# main.net
KiCad netlist of a schematic drawn in Altium Designer
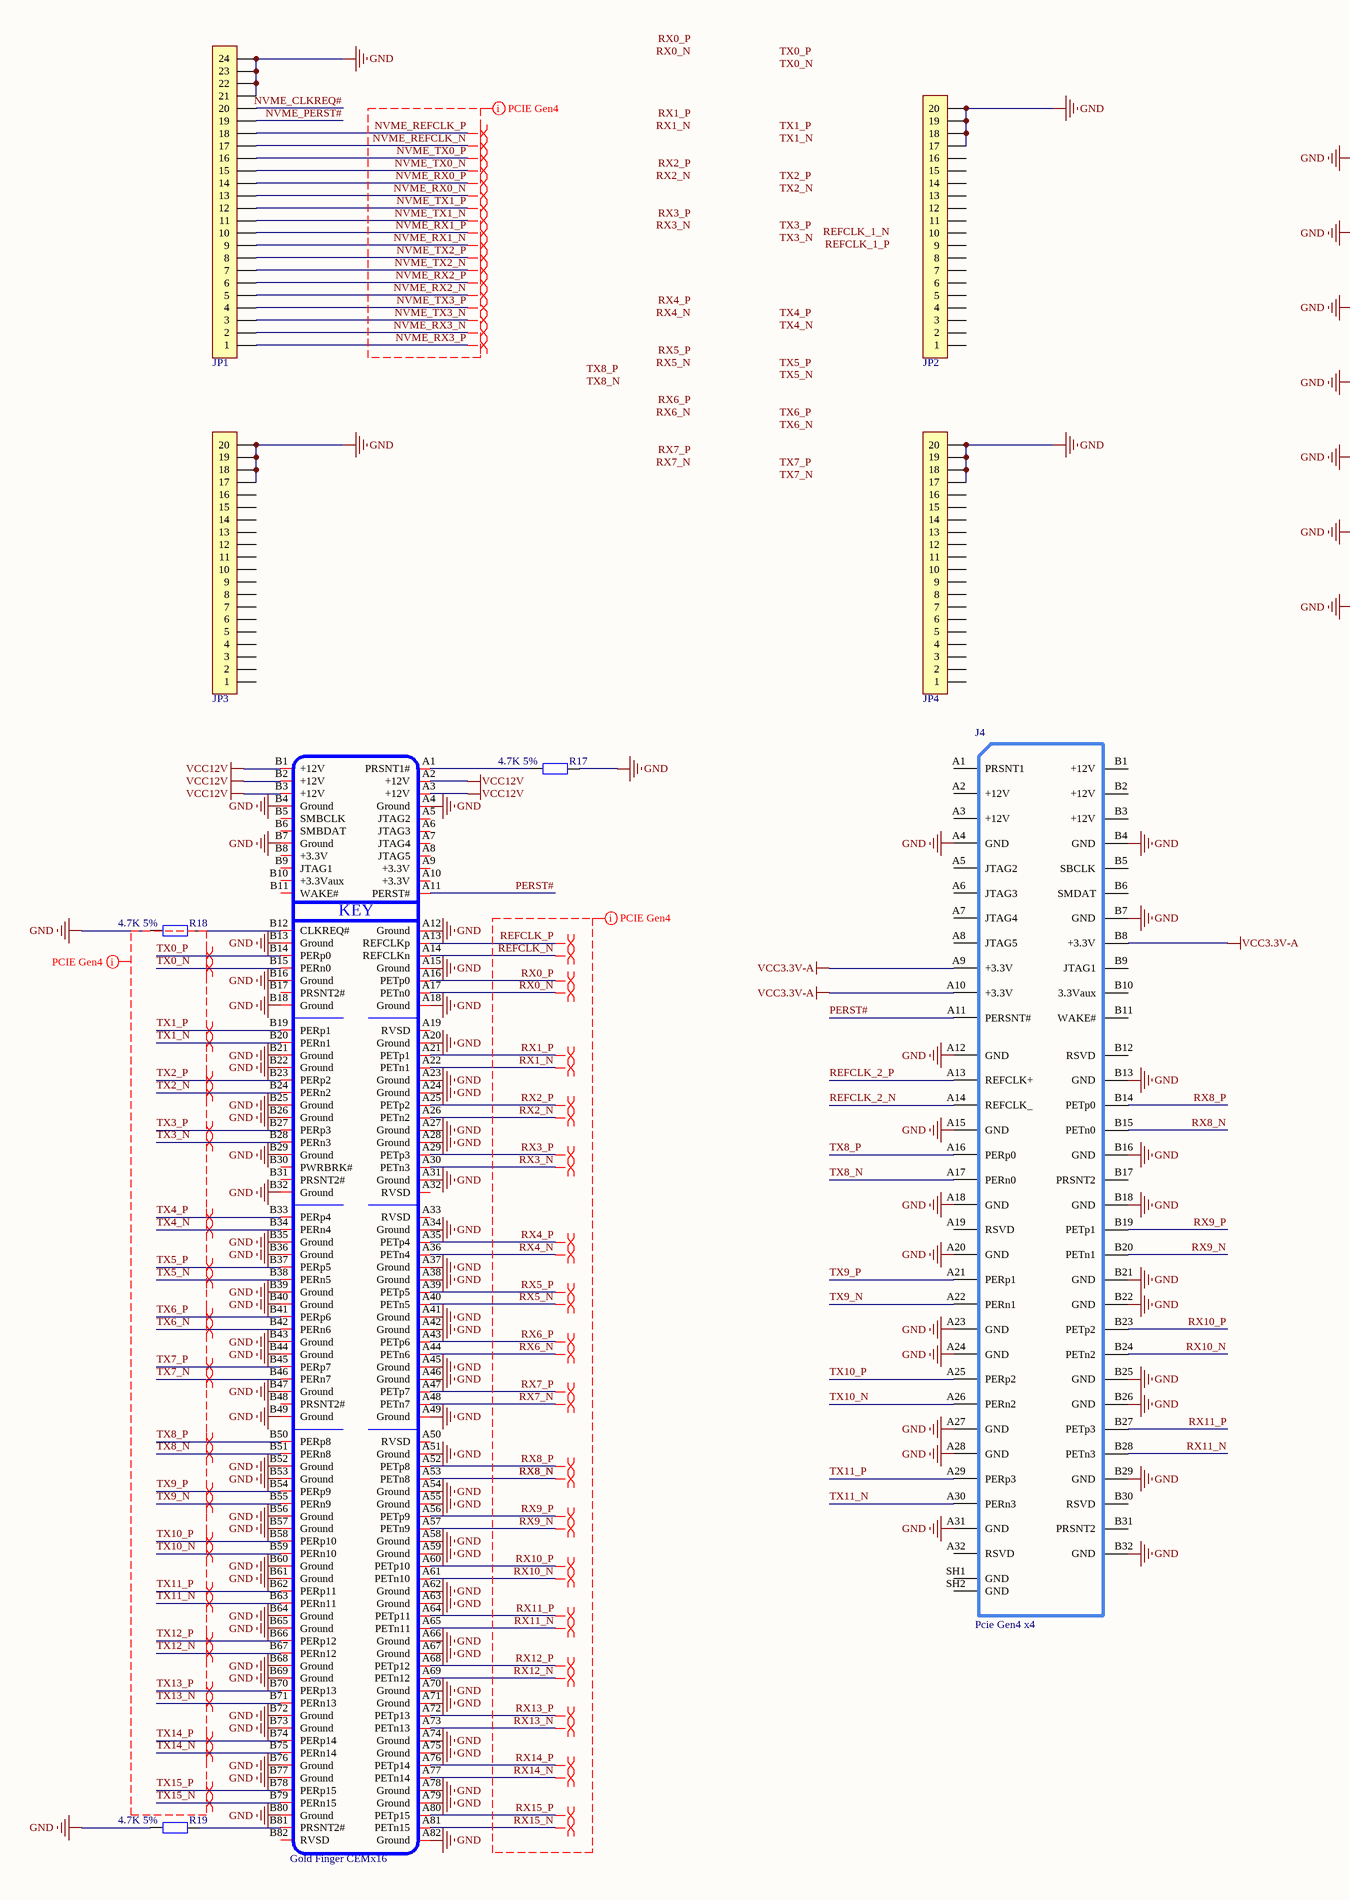
[diagram p0: main.SchDoc, left]
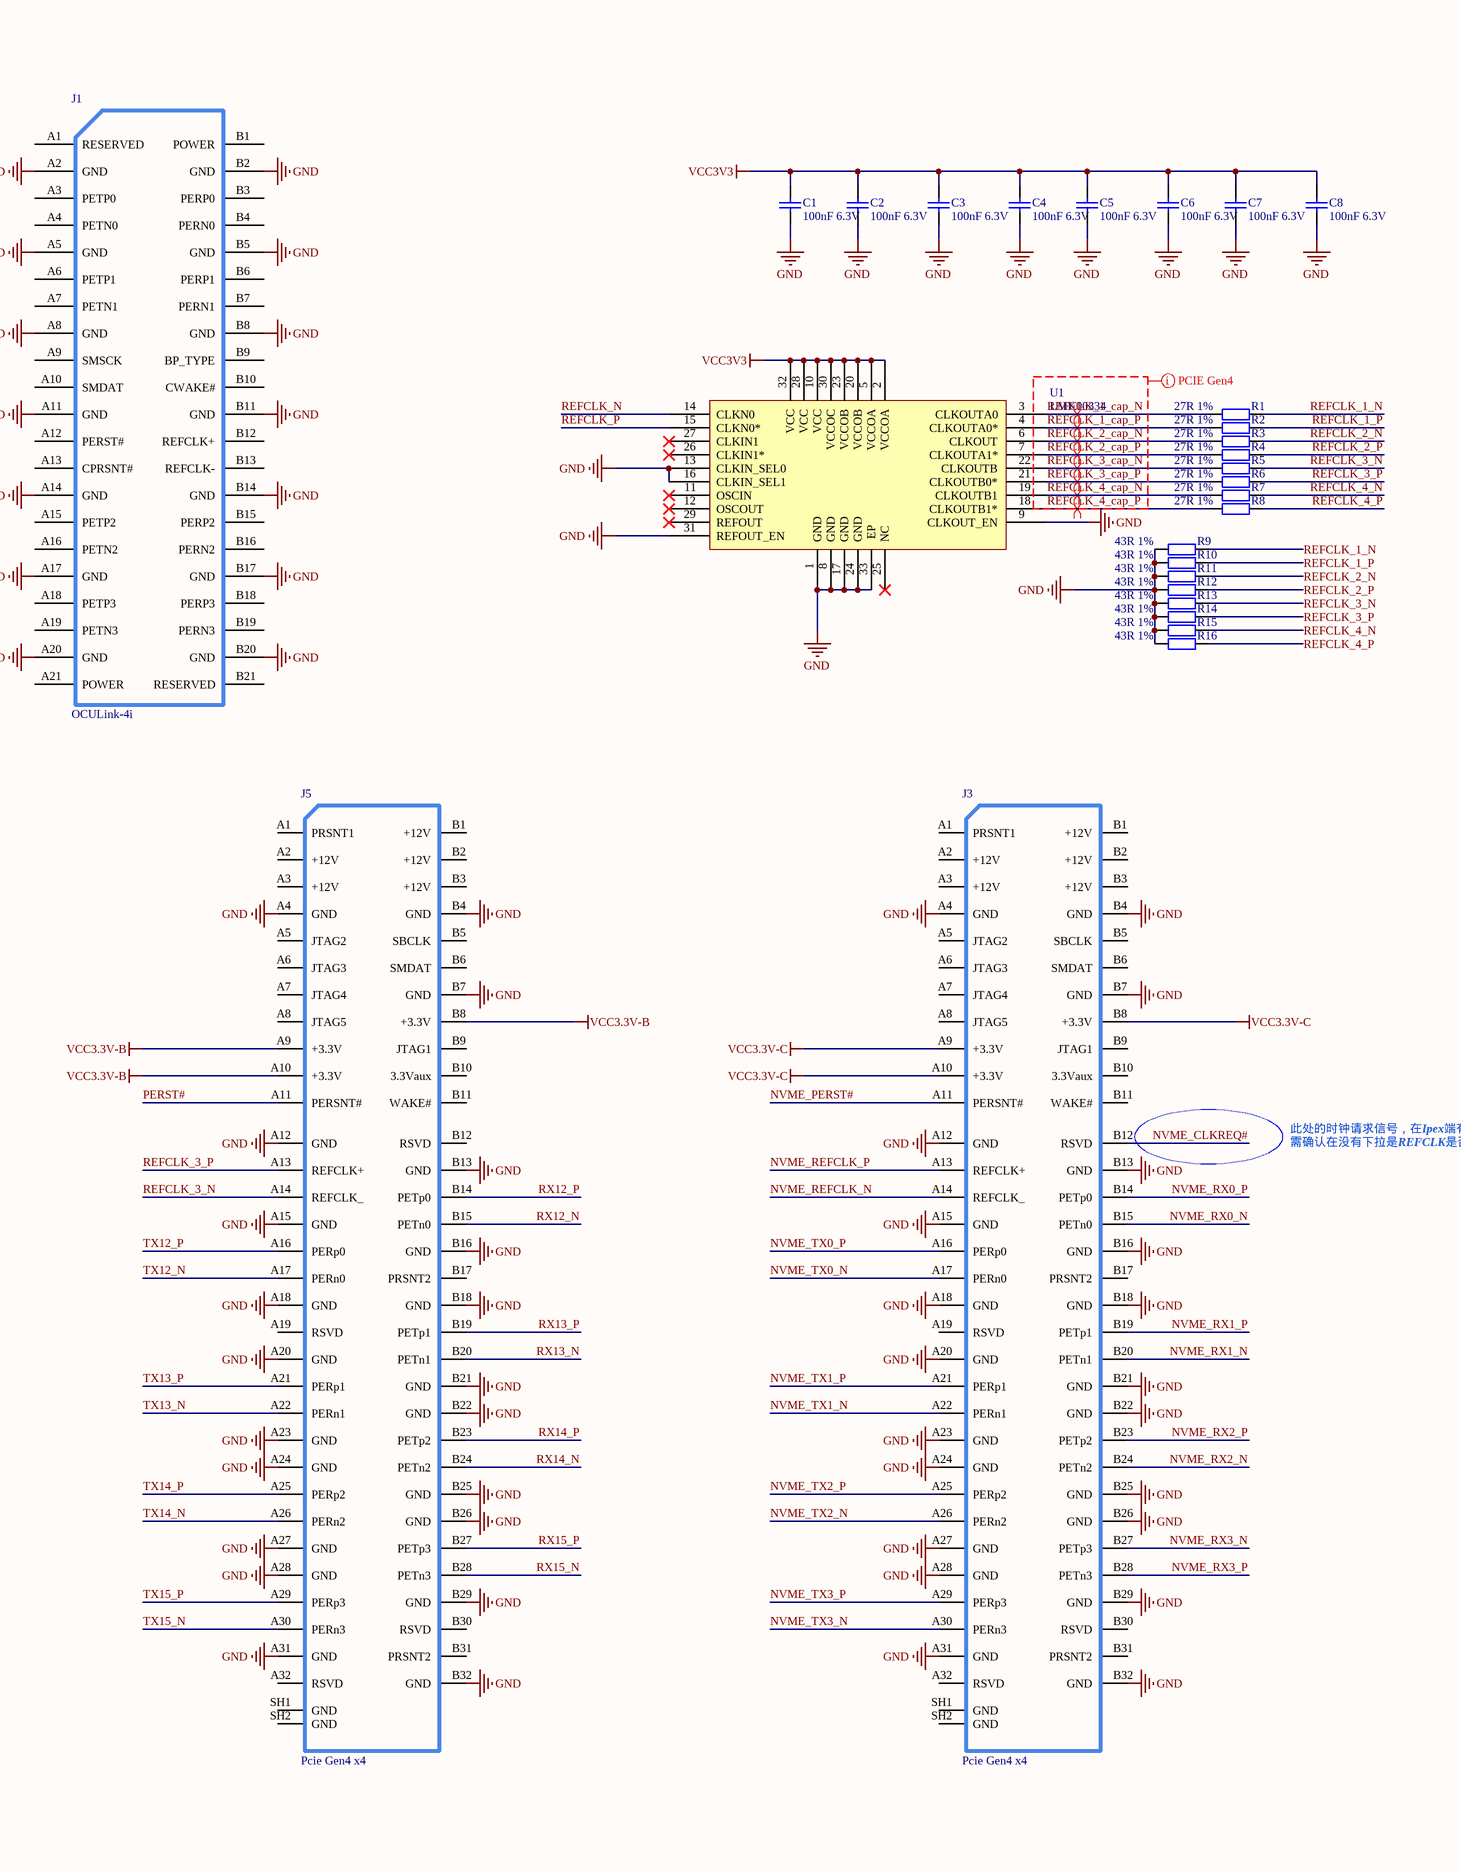
[diagram p1: main.SchDoc, right]

(export (version "E")
  (design (tool "Eeschema 10.0.6"))
  (components
    (comp (ref "C1")
      (value "100nF 6.3V")
      (footprint "c0603_l")
      (description "贴片电容/MLCC电容")
      (libsource (lib "Capacitors") (part "C"))
    )
    (comp (ref "C2")
      (value "100nF 6.3V")
      (footprint "c0603_l")
      (description "贴片电容/MLCC电容")
      (libsource (lib "Capacitors") (part "C"))
    )
    (comp (ref "C3")
      (value "100nF 6.3V")
      (footprint "c0603_l")
      (description "贴片电容/MLCC电容")
      (libsource (lib "Capacitors") (part "C"))
    )
    (comp (ref "C4")
      (value "100nF 6.3V")
      (footprint "c0603_l")
      (description "贴片电容/MLCC电容")
      (libsource (lib "Capacitors") (part "C"))
    )
    (comp (ref "C5")
      (value "100nF 6.3V")
      (footprint "c0603_l")
      (description "贴片电容/MLCC电容")
      (libsource (lib "Capacitors") (part "C"))
    )
    (comp (ref "C6")
      (value "100nF 6.3V")
      (footprint "c0603_l")
      (description "贴片电容/MLCC电容")
      (libsource (lib "Capacitors") (part "C"))
    )
    (comp (ref "C7")
      (value "100nF 6.3V")
      (footprint "c0603_l")
      (description "贴片电容/MLCC电容")
      (libsource (lib "Capacitors") (part "C"))
    )
    (comp (ref "C8")
      (value "100nF 6.3V")
      (footprint "c0603_l")
      (description "贴片电容/MLCC电容")
      (libsource (lib "Capacitors") (part "C"))
    )
    (comp (ref "J1")
      (value "OCULink-4i")
      (footprint "SFF8611_卧式")
      (libsource (lib "Connector-PCIE") (part "OCULink-4i"))
    )
    (comp (ref "J2")
      (value "Pcie Gen4 x16")
      (footprint "CON_PCI-E_164_M")
      (fields (field (name "DEVICE") "Gold Finger CEMx16"))
      (libsource (lib "Connector-PCIE") (part "Pcie Gen4 x16"))
    )
    (comp (ref "J3")
      (value "Pcie Gen4 x4")
      (footprint "PCIe Gen4 X4 贴片")
      (libsource (lib "Connector-PCIE") (part "Pcie Gen4 x4"))
    )
    (comp (ref "J4")
      (value "Pcie Gen4 x4")
      (footprint "PCIe Gen4 X4 贴片")
      (libsource (lib "Connector-PCIE") (part "Pcie Gen4 x4"))
    )
    (comp (ref "J5")
      (value "Pcie Gen4 x4")
      (footprint "PCIe Gen4 X4 贴片")
      (libsource (lib "Connector-PCIE") (part "Pcie Gen4 x4"))
    )
    (comp (ref "JP1")
      (value "FPC1.0-24P")
      (footprint "CONN-SMD_20P-P0.50_I-PEX_20455-020E-02")
      (description "FPC连接器")
      (fields (field (name "版权归属") "源创客"))
      (libsource (lib "Connector-FPC") (part "FPC-24P"))
    )
    (comp (ref "JP2")
      (value "FPC1.0-20P")
      (footprint "CONN-SMD_20P-P0.50_I-PEX_20455-020E-02")
      (description "FPC连接器")
      (fields (field (name "版权归属") "源创客"))
      (libsource (lib "Connector-FPC") (part "FPC-20P"))
    )
    (comp (ref "JP3")
      (value "FPC1.0-20P")
      (footprint "CONN-SMD_20P-P0.50_I-PEX_20455-020E-02")
      (description "FPC连接器")
      (fields (field (name "版权归属") "源创客"))
      (libsource (lib "Connector-FPC") (part "FPC-20P"))
    )
    (comp (ref "JP4")
      (value "FPC1.0-20P")
      (footprint "CONN-SMD_20P-P0.50_I-PEX_20455-020E-02")
      (description "FPC连接器")
      (fields (field (name "版权归属") "源创客"))
      (libsource (lib "Connector-FPC") (part "FPC-20P"))
    )
    (comp (ref "R1") (value "27R 1%") (footprint "r0402_l") (libsource (lib "Resistors") (part "R")))
    (comp (ref "R2") (value "27R 1%") (footprint "r0402_l") (libsource (lib "Resistors") (part "R")))
    (comp (ref "R3") (value "27R 1%") (footprint "r0402_l") (libsource (lib "Resistors") (part "R")))
    (comp (ref "R4") (value "27R 1%") (footprint "r0402_l") (libsource (lib "Resistors") (part "R")))
    (comp (ref "R5") (value "27R 1%") (footprint "r0402_l") (libsource (lib "Resistors") (part "R")))
    (comp (ref "R6") (value "27R 1%") (footprint "r0402_l") (libsource (lib "Resistors") (part "R")))
    (comp (ref "R7") (value "27R 1%") (footprint "r0402_l") (libsource (lib "Resistors") (part "R")))
    (comp (ref "R8") (value "27R 1%") (footprint "r0402_l") (libsource (lib "Resistors") (part "R")))
    (comp (ref "R9") (value "43R 1%") (footprint "r0402_l") (libsource (lib "Resistors") (part "R")))
    (comp (ref "R10") (value "43R 1%") (footprint "r0402_l") (libsource (lib "Resistors") (part "R")))
    (comp (ref "R11") (value "43R 1%") (footprint "r0402_l") (libsource (lib "Resistors") (part "R")))
    (comp (ref "R12") (value "43R 1%") (footprint "r0402_l") (libsource (lib "Resistors") (part "R")))
    (comp (ref "R13") (value "43R 1%") (footprint "r0402_l") (libsource (lib "Resistors") (part "R")))
    (comp (ref "R14") (value "43R 1%") (footprint "r0402_l") (libsource (lib "Resistors") (part "R")))
    (comp (ref "R15") (value "43R 1%") (footprint "r0402_l") (libsource (lib "Resistors") (part "R")))
    (comp (ref "R16") (value "43R 1%") (footprint "r0402_l") (libsource (lib "Resistors") (part "R")))
    (comp (ref "R17") (value "4.7K 5%") (footprint "r0402_l") (libsource (lib "Resistors") (part "R")))
    (comp (ref "R18") (value "4.7K 5%") (footprint "r0402_l") (libsource (lib "Resistors") (part "R")))
    (comp (ref "R19") (value "4.7K 5%") (footprint "r0402_l") (libsource (lib "Resistors") (part "R")))
    (comp (ref "U1") (value "LMK00334") (footprint "QFN32 5x5_N") (libsource (lib "时钟缓冲器") (part "LMK00334")))
  )
  (nets
    (net (code "1") (name "/NVME_CLKREQ#") (class "Default")
      (node (ref "J3") (pin "B12") (pinfunction "RSVD_B12") (pintype "passive"))
      (node (ref "JP1") (pin "20") (pinfunction "20_20") (pintype "passive"))
    )
    (net (code "2") (name "/NVME_PERST#") (class "Default")
      (node (ref "J3") (pin "A11") (pinfunction "PERSNT#_A11") (pintype "passive"))
      (node (ref "JP1") (pin "19") (pinfunction "19_19") (pintype "passive"))
    )
    (net (code "3") (name "/NVME_REFCLK_N") (class "Default")
      (node (ref "J3") (pin "A14") (pinfunction "REFCLK__A14") (pintype "passive"))
      (node (ref "JP1") (pin "17") (pinfunction "17_17") (pintype "passive"))
    )
    (net (code "4") (name "/NVME_REFCLK_P") (class "Default")
      (node (ref "J3") (pin "A13") (pinfunction "REFCLK+_A13") (pintype "passive"))
      (node (ref "JP1") (pin "18") (pinfunction "18_18") (pintype "passive"))
    )
    (net (code "5") (name "/NVME_RX0_N") (class "Default")
      (node (ref "J3") (pin "B15") (pinfunction "PETn0_B15") (pintype "passive"))
      (node (ref "JP1") (pin "13") (pinfunction "13_13") (pintype "passive"))
    )
    (net (code "6") (name "/NVME_RX0_P") (class "Default")
      (node (ref "J3") (pin "B14") (pinfunction "PETp0_B14") (pintype "passive"))
      (node (ref "JP1") (pin "14") (pinfunction "14_14") (pintype "passive"))
    )
    (net (code "7") (name "/NVME_RX1_N") (class "Default")
      (node (ref "J3") (pin "B20") (pinfunction "PETn1_B20") (pintype "passive"))
      (node (ref "JP1") (pin "9") (pinfunction "9_9") (pintype "passive"))
    )
    (net (code "8") (name "/NVME_RX1_P") (class "Default")
      (node (ref "J3") (pin "B19") (pinfunction "PETp1_B19") (pintype "passive"))
      (node (ref "JP1") (pin "10") (pinfunction "10_10") (pintype "passive"))
    )
    (net (code "9") (name "/NVME_RX2_N") (class "Default")
      (node (ref "J3") (pin "B24") (pinfunction "PETn2_B24") (pintype "passive"))
      (node (ref "JP1") (pin "5") (pinfunction "5_5") (pintype "passive"))
    )
    (net (code "10") (name "/NVME_RX2_P") (class "Default")
      (node (ref "J3") (pin "B23") (pinfunction "PETp2_B23") (pintype "passive"))
      (node (ref "JP1") (pin "6") (pinfunction "6_6") (pintype "passive"))
    )
    (net (code "11") (name "/NVME_RX3_N") (class "Default")
      (node (ref "J3") (pin "B27") (pinfunction "PETp3_B27") (pintype "passive"))
      (node (ref "JP1") (pin "2") (pinfunction "2_2") (pintype "passive"))
    )
    (net (code "12") (name "/NVME_RX3_P") (class "Default")
      (node (ref "J3") (pin "B28") (pinfunction "PETn3_B28") (pintype "passive"))
      (node (ref "JP1") (pin "1") (pinfunction "1_1") (pintype "passive"))
    )
    (net (code "13") (name "/NVME_TX0_N") (class "Default")
      (node (ref "J3") (pin "A17") (pinfunction "PERn0_A17") (pintype "passive"))
      (node (ref "JP1") (pin "15") (pinfunction "15_15") (pintype "passive"))
    )
    (net (code "14") (name "/NVME_TX0_P") (class "Default")
      (node (ref "J3") (pin "A16") (pinfunction "PERp0_A16") (pintype "passive"))
      (node (ref "JP1") (pin "16") (pinfunction "16_16") (pintype "passive"))
    )
    (net (code "15") (name "/NVME_TX1_N") (class "Default")
      (node (ref "J3") (pin "A22") (pinfunction "PERn1_A22") (pintype "passive"))
      (node (ref "JP1") (pin "11") (pinfunction "11_11") (pintype "passive"))
    )
    (net (code "16") (name "/NVME_TX1_P") (class "Default")
      (node (ref "J3") (pin "A21") (pinfunction "PERp1_A21") (pintype "passive"))
      (node (ref "JP1") (pin "12") (pinfunction "12_12") (pintype "passive"))
    )
    (net (code "17") (name "/NVME_TX2_N") (class "Default")
      (node (ref "J3") (pin "A26") (pinfunction "PERn2_A26") (pintype "passive"))
      (node (ref "JP1") (pin "7") (pinfunction "7_7") (pintype "passive"))
    )
    (net (code "18") (name "/NVME_TX2_P") (class "Default")
      (node (ref "J3") (pin "A25") (pinfunction "PERp2_A25") (pintype "passive"))
      (node (ref "JP1") (pin "8") (pinfunction "8_8") (pintype "passive"))
    )
    (net (code "19") (name "/NVME_TX3_N") (class "Default")
      (node (ref "J3") (pin "A30") (pinfunction "PERn3_A30") (pintype "passive"))
      (node (ref "JP1") (pin "3") (pinfunction "3_3") (pintype "passive"))
    )
    (net (code "20") (name "/NVME_TX3_P") (class "Default")
      (node (ref "J3") (pin "A29") (pinfunction "PERp3_A29") (pintype "passive"))
      (node (ref "JP1") (pin "4") (pinfunction "4_4") (pintype "passive"))
    )
    (net (code "21") (name "/PERST#") (class "Default")
      (node (ref "J2") (pin "A11") (pinfunction "PERST#_A11") (pintype "passive"))
      (node (ref "J4") (pin "A11") (pinfunction "PERSNT#_A11") (pintype "passive"))
      (node (ref "J5") (pin "A11") (pinfunction "PERSNT#_A11") (pintype "passive"))
    )
    (net (code "22") (name "/REFCLK_1_N") (class "Default")
      (node (ref "R1") (pin "1") (pinfunction "1_1") (pintype "passive"))
      (node (ref "R9") (pin "1") (pinfunction "1_1") (pintype "passive"))
    )
    (net (code "23") (name "/REFCLK_1_P") (class "Default")
      (node (ref "R10") (pin "1") (pinfunction "1_1") (pintype "passive"))
      (node (ref "R2") (pin "1") (pinfunction "1_1") (pintype "passive"))
    )
    (net (code "24") (name "/REFCLK_1_cap_N") (class "Default")
      (node (ref "R1") (pin "2") (pinfunction "2_2") (pintype "passive"))
      (node (ref "U1") (pin "3") (pinfunction "CLKOUTA0_3") (pintype "passive"))
    )
    (net (code "25") (name "/REFCLK_1_cap_P") (class "Default")
      (node (ref "R2") (pin "2") (pinfunction "2_2") (pintype "passive"))
      (node (ref "U1") (pin "4") (pinfunction "CLKOUTA0*_4") (pintype "passive"))
    )
    (net (code "26") (name "/REFCLK_2_N") (class "Default")
      (node (ref "J4") (pin "A14") (pinfunction "REFCLK__A14") (pintype "passive"))
      (node (ref "R11") (pin "1") (pinfunction "1_1") (pintype "passive"))
      (node (ref "R3") (pin "1") (pinfunction "1_1") (pintype "passive"))
    )
    (net (code "27") (name "/REFCLK_2_P") (class "Default")
      (node (ref "J4") (pin "A13") (pinfunction "REFCLK+_A13") (pintype "passive"))
      (node (ref "R12") (pin "1") (pinfunction "1_1") (pintype "passive"))
      (node (ref "R4") (pin "1") (pinfunction "1_1") (pintype "passive"))
    )
    (net (code "28") (name "/REFCLK_2_cap_N") (class "Default")
      (node (ref "R3") (pin "2") (pinfunction "2_2") (pintype "passive"))
      (node (ref "U1") (pin "6") (pinfunction "CLKOUT_6") (pintype "passive"))
    )
    (net (code "29") (name "/REFCLK_2_cap_P") (class "Default")
      (node (ref "R4") (pin "2") (pinfunction "2_2") (pintype "passive"))
      (node (ref "U1") (pin "7") (pinfunction "CLKOUTA1*_7") (pintype "passive"))
    )
    (net (code "30") (name "/REFCLK_3_N") (class "Default")
      (node (ref "J5") (pin "A14") (pinfunction "REFCLK__A14") (pintype "passive"))
      (node (ref "R13") (pin "1") (pinfunction "1_1") (pintype "passive"))
      (node (ref "R5") (pin "1") (pinfunction "1_1") (pintype "passive"))
    )
    (net (code "31") (name "/REFCLK_3_P") (class "Default")
      (node (ref "J5") (pin "A13") (pinfunction "REFCLK+_A13") (pintype "passive"))
      (node (ref "R14") (pin "1") (pinfunction "1_1") (pintype "passive"))
      (node (ref "R6") (pin "1") (pinfunction "1_1") (pintype "passive"))
    )
    (net (code "32") (name "/REFCLK_3_cap_N") (class "Default")
      (node (ref "R5") (pin "2") (pinfunction "2_2") (pintype "passive"))
      (node (ref "U1") (pin "22") (pinfunction "CLKOUTB_22") (pintype "passive"))
    )
    (net (code "33") (name "/REFCLK_3_cap_P") (class "Default")
      (node (ref "R6") (pin "2") (pinfunction "2_2") (pintype "passive"))
      (node (ref "U1") (pin "21") (pinfunction "CLKOUTB0*_21") (pintype "passive"))
    )
    (net (code "34") (name "/REFCLK_4_N") (class "Default")
      (node (ref "R15") (pin "1") (pinfunction "1_1") (pintype "passive"))
      (node (ref "R7") (pin "1") (pinfunction "1_1") (pintype "passive"))
    )
    (net (code "35") (name "/REFCLK_4_P") (class "Default")
      (node (ref "R16") (pin "1") (pinfunction "1_1") (pintype "passive"))
      (node (ref "R8") (pin "1") (pinfunction "1_1") (pintype "passive"))
    )
    (net (code "36") (name "/REFCLK_4_cap_N") (class "Default")
      (node (ref "R7") (pin "2") (pinfunction "2_2") (pintype "passive"))
      (node (ref "U1") (pin "19") (pinfunction "CLKOUTB1_19") (pintype "passive"))
    )
    (net (code "37") (name "/REFCLK_4_cap_P") (class "Default")
      (node (ref "R8") (pin "2") (pinfunction "2_2") (pintype "passive"))
      (node (ref "U1") (pin "18") (pinfunction "CLKOUTB1*_18") (pintype "passive"))
    )
    (net (code "38") (name "/REFCLK_N") (class "Default")
      (node (ref "J2") (pin "A14") (pinfunction "REFCLKn_A14") (pintype "passive"))
      (node (ref "U1") (pin "14") (pinfunction "CLKN0_14") (pintype "passive"))
    )
    (net (code "39") (name "/REFCLK_P") (class "Default")
      (node (ref "J2") (pin "A13") (pinfunction "REFCLKp_A13") (pintype "passive"))
      (node (ref "U1") (pin "15") (pinfunction "CLKN0*_15") (pintype "passive"))
    )
    (net (code "40") (name "/RX0_N") (class "Default")
      (node (ref "J2") (pin "A17") (pinfunction "PETn0_A17") (pintype "passive"))
    )
    (net (code "41") (name "/RX0_P") (class "Default")
      (node (ref "J2") (pin "A16") (pinfunction "PETp0_A16") (pintype "passive"))
    )
    (net (code "42") (name "/RX1_N") (class "Default")
      (node (ref "J2") (pin "A22") (pinfunction "PETn1_A22") (pintype "passive"))
    )
    (net (code "43") (name "/RX1_P") (class "Default")
      (node (ref "J2") (pin "A21") (pinfunction "PETp1_A21") (pintype "passive"))
    )
    (net (code "44") (name "/RX2_N") (class "Default")
      (node (ref "J2") (pin "A26") (pinfunction "PETn2_A26") (pintype "passive"))
    )
    (net (code "45") (name "/RX2_P") (class "Default")
      (node (ref "J2") (pin "A25") (pinfunction "PETp2_A25") (pintype "passive"))
    )
    (net (code "46") (name "/RX3_N") (class "Default")
      (node (ref "J2") (pin "A30") (pinfunction "PETn3_A30") (pintype "passive"))
    )
    (net (code "47") (name "/RX3_P") (class "Default")
      (node (ref "J2") (pin "A29") (pinfunction "PETp3_A29") (pintype "passive"))
    )
    (net (code "48") (name "/RX4_N") (class "Default")
      (node (ref "J2") (pin "A36") (pinfunction "PETn4_A36") (pintype "passive"))
    )
    (net (code "49") (name "/RX4_P") (class "Default")
      (node (ref "J2") (pin "A35") (pinfunction "PETp4_A35") (pintype "passive"))
    )
    (net (code "50") (name "/RX5_N") (class "Default")
      (node (ref "J2") (pin "A40") (pinfunction "PETn5_A40") (pintype "passive"))
    )
    (net (code "51") (name "/RX5_P") (class "Default")
      (node (ref "J2") (pin "A39") (pinfunction "PETp5_A39") (pintype "passive"))
    )
    (net (code "52") (name "/RX6_N") (class "Default")
      (node (ref "J2") (pin "A44") (pinfunction "PETn6_A44") (pintype "passive"))
    )
    (net (code "53") (name "/RX6_P") (class "Default")
      (node (ref "J2") (pin "A43") (pinfunction "PETp6_A43") (pintype "passive"))
    )
    (net (code "54") (name "/RX7_N") (class "Default")
      (node (ref "J2") (pin "A48") (pinfunction "PETn7_A48") (pintype "passive"))
    )
    (net (code "55") (name "/RX7_P") (class "Default")
      (node (ref "J2") (pin "A47") (pinfunction "PETp7_A47") (pintype "passive"))
    )
    (net (code "56") (name "/RX8_N") (class "Default")
      (node (ref "J2") (pin "A53") (pinfunction "PETn8_A53") (pintype "passive"))
      (node (ref "J4") (pin "B15") (pinfunction "PETn0_B15") (pintype "passive"))
    )
    (net (code "57") (name "/RX8_P") (class "Default")
      (node (ref "J2") (pin "A52") (pinfunction "PETp8_A52") (pintype "passive"))
      (node (ref "J4") (pin "B14") (pinfunction "PETp0_B14") (pintype "passive"))
    )
    (net (code "58") (name "/RX9_N") (class "Default")
      (node (ref "J2") (pin "A57") (pinfunction "PETn9_A57") (pintype "passive"))
      (node (ref "J4") (pin "B20") (pinfunction "PETn1_B20") (pintype "passive"))
    )
    (net (code "59") (name "/RX9_P") (class "Default")
      (node (ref "J2") (pin "A56") (pinfunction "PETp9_A56") (pintype "passive"))
      (node (ref "J4") (pin "B19") (pinfunction "PETp1_B19") (pintype "passive"))
    )
    (net (code "60") (name "/RX10_N") (class "Default")
      (node (ref "J2") (pin "A61") (pinfunction "PETn10_A61") (pintype "passive"))
      (node (ref "J4") (pin "B24") (pinfunction "PETn2_B24") (pintype "passive"))
    )
    (net (code "61") (name "/RX10_P") (class "Default")
      (node (ref "J2") (pin "A60") (pinfunction "PETp10_A60") (pintype "passive"))
      (node (ref "J4") (pin "B23") (pinfunction "PETp2_B23") (pintype "passive"))
    )
    (net (code "62") (name "/RX11_N") (class "Default")
      (node (ref "J2") (pin "A65") (pinfunction "PETn11_A65") (pintype "passive"))
      (node (ref "J4") (pin "B28") (pinfunction "PETn3_B28") (pintype "passive"))
    )
    (net (code "63") (name "/RX11_P") (class "Default")
      (node (ref "J2") (pin "A64") (pinfunction "PETp11_A64") (pintype "passive"))
      (node (ref "J4") (pin "B27") (pinfunction "PETp3_B27") (pintype "passive"))
    )
    (net (code "64") (name "/RX12_N") (class "Default")
      (node (ref "J2") (pin "A69") (pinfunction "PETn12_A69") (pintype "passive"))
      (node (ref "J5") (pin "B15") (pinfunction "PETn0_B15") (pintype "passive"))
    )
    (net (code "65") (name "/RX12_P") (class "Default")
      (node (ref "J2") (pin "A68") (pinfunction "PETp12_A68") (pintype "passive"))
      (node (ref "J5") (pin "B14") (pinfunction "PETp0_B14") (pintype "passive"))
    )
    (net (code "66") (name "/RX13_N") (class "Default")
      (node (ref "J2") (pin "A73") (pinfunction "PETn13_A73") (pintype "passive"))
      (node (ref "J5") (pin "B20") (pinfunction "PETn1_B20") (pintype "passive"))
    )
    (net (code "67") (name "/RX13_P") (class "Default")
      (node (ref "J2") (pin "A72") (pinfunction "PETp13_A72") (pintype "passive"))
      (node (ref "J5") (pin "B19") (pinfunction "PETp1_B19") (pintype "passive"))
    )
    (net (code "68") (name "/RX14_N") (class "Default")
      (node (ref "J2") (pin "A77") (pinfunction "PETn14_A77") (pintype "passive"))
      (node (ref "J5") (pin "B24") (pinfunction "PETn2_B24") (pintype "passive"))
    )
    (net (code "69") (name "/RX14_P") (class "Default")
      (node (ref "J2") (pin "A76") (pinfunction "PETp14_A76") (pintype "passive"))
      (node (ref "J5") (pin "B23") (pinfunction "PETp2_B23") (pintype "passive"))
    )
    (net (code "70") (name "/RX15_N") (class "Default")
      (node (ref "J2") (pin "A81") (pinfunction "PETn15_A81") (pintype "passive"))
      (node (ref "J5") (pin "B28") (pinfunction "PETn3_B28") (pintype "passive"))
    )
    (net (code "71") (name "/RX15_P") (class "Default")
      (node (ref "J2") (pin "A80") (pinfunction "PETp15_A80") (pintype "passive"))
      (node (ref "J5") (pin "B27") (pinfunction "PETp3_B27") (pintype "passive"))
    )
    (net (code "72") (name "/TX0_N") (class "Default")
      (node (ref "J2") (pin "B15") (pinfunction "PERn0_B15") (pintype "passive"))
    )
    (net (code "73") (name "/TX0_P") (class "Default")
      (node (ref "J2") (pin "B14") (pinfunction "PERp0_B14") (pintype "passive"))
    )
    (net (code "74") (name "/TX1_N") (class "Default")
      (node (ref "J2") (pin "B20") (pinfunction "PERn1_B20") (pintype "passive"))
    )
    (net (code "75") (name "/TX1_P") (class "Default")
      (node (ref "J2") (pin "B19") (pinfunction "PERp1_B19") (pintype "passive"))
    )
    (net (code "76") (name "/TX2_N") (class "Default")
      (node (ref "J2") (pin "B24") (pinfunction "PERn2_B24") (pintype "passive"))
    )
    (net (code "77") (name "/TX2_P") (class "Default")
      (node (ref "J2") (pin "B23") (pinfunction "PERp2_B23") (pintype "passive"))
    )
    (net (code "78") (name "/TX3_N") (class "Default")
      (node (ref "J2") (pin "B28") (pinfunction "PERn3_B28") (pintype "passive"))
    )
    (net (code "79") (name "/TX3_P") (class "Default")
      (node (ref "J2") (pin "B27") (pinfunction "PERp3_B27") (pintype "passive"))
    )
    (net (code "80") (name "/TX4_N") (class "Default")
      (node (ref "J2") (pin "B34") (pinfunction "PERn4_B34") (pintype "passive"))
    )
    (net (code "81") (name "/TX4_P") (class "Default")
      (node (ref "J2") (pin "B33") (pinfunction "PERp4_B33") (pintype "passive"))
    )
    (net (code "82") (name "/TX5_N") (class "Default")
      (node (ref "J2") (pin "B38") (pinfunction "PERn5_B38") (pintype "passive"))
    )
    (net (code "83") (name "/TX5_P") (class "Default")
      (node (ref "J2") (pin "B37") (pinfunction "PERp5_B37") (pintype "passive"))
    )
    (net (code "84") (name "/TX6_N") (class "Default")
      (node (ref "J2") (pin "B42") (pinfunction "PERn6_B42") (pintype "passive"))
    )
    (net (code "85") (name "/TX6_P") (class "Default")
      (node (ref "J2") (pin "B41") (pinfunction "PERp6_B41") (pintype "passive"))
    )
    (net (code "86") (name "/TX7_N") (class "Default")
      (node (ref "J2") (pin "B46") (pinfunction "PERn7_B46") (pintype "passive"))
    )
    (net (code "87") (name "/TX7_P") (class "Default")
      (node (ref "J2") (pin "B45") (pinfunction "PERp7_B45") (pintype "passive"))
    )
    (net (code "88") (name "/TX8_N") (class "Default")
      (node (ref "J2") (pin "B51") (pinfunction "PERn8_B51") (pintype "passive"))
      (node (ref "J4") (pin "A17") (pinfunction "PERn0_A17") (pintype "passive"))
    )
    (net (code "89") (name "/TX8_P") (class "Default")
      (node (ref "J2") (pin "B50") (pinfunction "PERp8_B50") (pintype "passive"))
      (node (ref "J4") (pin "A16") (pinfunction "PERp0_A16") (pintype "passive"))
    )
    (net (code "90") (name "/TX9_N") (class "Default")
      (node (ref "J2") (pin "B55") (pinfunction "PERn9_B55") (pintype "passive"))
      (node (ref "J4") (pin "A22") (pinfunction "PERn1_A22") (pintype "passive"))
    )
    (net (code "91") (name "/TX9_P") (class "Default")
      (node (ref "J2") (pin "B54") (pinfunction "PERp9_B54") (pintype "passive"))
      (node (ref "J4") (pin "A21") (pinfunction "PERp1_A21") (pintype "passive"))
    )
    (net (code "92") (name "/TX10_N") (class "Default")
      (node (ref "J2") (pin "B59") (pinfunction "PERn10_B59") (pintype "passive"))
      (node (ref "J4") (pin "A26") (pinfunction "PERn2_A26") (pintype "passive"))
    )
    (net (code "93") (name "/TX10_P") (class "Default")
      (node (ref "J2") (pin "B58") (pinfunction "PERp10_B58") (pintype "passive"))
      (node (ref "J4") (pin "A25") (pinfunction "PERp2_A25") (pintype "passive"))
    )
    (net (code "94") (name "/TX11_N") (class "Default")
      (node (ref "J2") (pin "B63") (pinfunction "PERn11_B63") (pintype "passive"))
      (node (ref "J4") (pin "A30") (pinfunction "PERn3_A30") (pintype "passive"))
    )
    (net (code "95") (name "/TX11_P") (class "Default")
      (node (ref "J2") (pin "B62") (pinfunction "PERp11_B62") (pintype "passive"))
      (node (ref "J4") (pin "A29") (pinfunction "PERp3_A29") (pintype "passive"))
    )
    (net (code "96") (name "/TX12_N") (class "Default")
      (node (ref "J2") (pin "B67") (pinfunction "PERn12_B67") (pintype "passive"))
      (node (ref "J5") (pin "A17") (pinfunction "PERn0_A17") (pintype "passive"))
    )
    (net (code "97") (name "/TX12_P") (class "Default")
      (node (ref "J2") (pin "B66") (pinfunction "PERp12_B66") (pintype "passive"))
      (node (ref "J5") (pin "A16") (pinfunction "PERp0_A16") (pintype "passive"))
    )
    (net (code "98") (name "/TX13_N") (class "Default")
      (node (ref "J2") (pin "B71") (pinfunction "PERn13_B71") (pintype "passive"))
      (node (ref "J5") (pin "A22") (pinfunction "PERn1_A22") (pintype "passive"))
    )
    (net (code "99") (name "/TX13_P") (class "Default")
      (node (ref "J2") (pin "B70") (pinfunction "PERp13_B70") (pintype "passive"))
      (node (ref "J5") (pin "A21") (pinfunction "PERp1_A21") (pintype "passive"))
    )
    (net (code "100") (name "/TX14_N") (class "Default")
      (node (ref "J2") (pin "B75") (pinfunction "PERn14_B75") (pintype "passive"))
      (node (ref "J5") (pin "A26") (pinfunction "PERn2_A26") (pintype "passive"))
    )
    (net (code "101") (name "/TX14_P") (class "Default")
      (node (ref "J2") (pin "B74") (pinfunction "PERp14_B74") (pintype "passive"))
      (node (ref "J5") (pin "A25") (pinfunction "PERp2_A25") (pintype "passive"))
    )
    (net (code "102") (name "/TX15_N") (class "Default")
      (node (ref "J2") (pin "B79") (pinfunction "PERn15_B79") (pintype "passive"))
      (node (ref "J5") (pin "A30") (pinfunction "PERn3_A30") (pintype "passive"))
    )
    (net (code "103") (name "/TX15_P") (class "Default")
      (node (ref "J2") (pin "B78") (pinfunction "PERp15_B78") (pintype "passive"))
      (node (ref "J5") (pin "A29") (pinfunction "PERp3_A29") (pintype "passive"))
    )
    (net (code "104") (name "GND") (class "Default")
      (node (ref "C1") (pin "1") (pinfunction "1_1") (pintype "passive"))
      (node (ref "C2") (pin "1") (pinfunction "1_1") (pintype "passive"))
      (node (ref "C3") (pin "1") (pinfunction "1_1") (pintype "passive"))
      (node (ref "C4") (pin "1") (pinfunction "1_1") (pintype "passive"))
      (node (ref "C5") (pin "1") (pinfunction "1_1") (pintype "passive"))
      (node (ref "C6") (pin "1") (pinfunction "1_1") (pintype "passive"))
      (node (ref "C7") (pin "1") (pinfunction "1_1") (pintype "passive"))
      (node (ref "C8") (pin "1") (pinfunction "1_1") (pintype "passive"))
      (node (ref "J1") (pin "A11") (pinfunction "GND_A11") (pintype "passive"))
      (node (ref "J1") (pin "A14") (pinfunction "GND_A14") (pintype "passive"))
      (node (ref "J1") (pin "A17") (pinfunction "GND_A17") (pintype "passive"))
      (node (ref "J1") (pin "A2") (pinfunction "GND_A2") (pintype "passive"))
      (node (ref "J1") (pin "A20") (pinfunction "GND_A20") (pintype "passive"))
      (node (ref "J1") (pin "A5") (pinfunction "GND_A5") (pintype "passive"))
      (node (ref "J1") (pin "A8") (pinfunction "GND_A8") (pintype "passive"))
      (node (ref "J1") (pin "B11") (pinfunction "GND_B11") (pintype "passive"))
      (node (ref "J1") (pin "B14") (pinfunction "GND_B14") (pintype "passive"))
      (node (ref "J1") (pin "B17") (pinfunction "GND_B17") (pintype "passive"))
      (node (ref "J1") (pin "B2") (pinfunction "GND_B2") (pintype "passive"))
      (node (ref "J1") (pin "B20") (pinfunction "GND_B20") (pintype "passive"))
      (node (ref "J1") (pin "B5") (pinfunction "GND_B5") (pintype "passive"))
      (node (ref "J1") (pin "B8") (pinfunction "GND_B8") (pintype "passive"))
      (node (ref "J2") (pin "A12") (pinfunction "Ground_A12") (pintype "passive"))
      (node (ref "J2") (pin "A15") (pinfunction "Ground_A15") (pintype "passive"))
      (node (ref "J2") (pin "A18") (pinfunction "Ground_A18") (pintype "passive"))
      (node (ref "J2") (pin "A20") (pinfunction "Ground_A20") (pintype "passive"))
      (node (ref "J2") (pin "A23") (pinfunction "Ground_A23") (pintype "passive"))
      (node (ref "J2") (pin "A24") (pinfunction "Ground_A24") (pintype "passive"))
      (node (ref "J2") (pin "A27") (pinfunction "Ground_A27") (pintype "passive"))
      (node (ref "J2") (pin "A28") (pinfunction "Ground_A28") (pintype "passive"))
      (node (ref "J2") (pin "A31") (pinfunction "Ground_A31") (pintype "passive"))
      (node (ref "J2") (pin "A34") (pinfunction "Ground_A34") (pintype "passive"))
      (node (ref "J2") (pin "A37") (pinfunction "Ground_A37") (pintype "passive"))
      (node (ref "J2") (pin "A38") (pinfunction "Ground_A38") (pintype "passive"))
      (node (ref "J2") (pin "A4") (pinfunction "Ground_A4") (pintype "passive"))
      (node (ref "J2") (pin "A41") (pinfunction "Ground_A41") (pintype "passive"))
      (node (ref "J2") (pin "A42") (pinfunction "Ground_A42") (pintype "passive"))
      (node (ref "J2") (pin "A45") (pinfunction "Ground_A45") (pintype "passive"))
      (node (ref "J2") (pin "A46") (pinfunction "Ground_A46") (pintype "passive"))
      (node (ref "J2") (pin "A49") (pinfunction "Ground_A49") (pintype "passive"))
      (node (ref "J2") (pin "A51") (pinfunction "Ground_A51") (pintype "passive"))
      (node (ref "J2") (pin "A54") (pinfunction "Ground_A54") (pintype "passive"))
      (node (ref "J2") (pin "A55") (pinfunction "Ground_A55") (pintype "passive"))
      (node (ref "J2") (pin "A58") (pinfunction "Ground_A58") (pintype "passive"))
      (node (ref "J2") (pin "A59") (pinfunction "Ground_A59") (pintype "passive"))
      (node (ref "J2") (pin "A62") (pinfunction "Ground_A62") (pintype "passive"))
      (node (ref "J2") (pin "A63") (pinfunction "Ground_A63") (pintype "passive"))
      (node (ref "J2") (pin "A66") (pinfunction "Ground_A66") (pintype "passive"))
      (node (ref "J2") (pin "A67") (pinfunction "Ground_A67") (pintype "passive"))
      (node (ref "J2") (pin "A70") (pinfunction "Ground_A70") (pintype "passive"))
      (node (ref "J2") (pin "A71") (pinfunction "Ground_A71") (pintype "passive"))
      (node (ref "J2") (pin "A74") (pinfunction "Ground_A74") (pintype "passive"))
      (node (ref "J2") (pin "A75") (pinfunction "Ground_A75") (pintype "passive"))
      (node (ref "J2") (pin "A78") (pinfunction "Ground_A78") (pintype "passive"))
      (node (ref "J2") (pin "A79") (pinfunction "Ground_A79") (pintype "passive"))
      (node (ref "J2") (pin "A82") (pinfunction "Ground_A82") (pintype "passive"))
      (node (ref "J2") (pin "B13") (pinfunction "Ground_B13") (pintype "passive"))
      (node (ref "J2") (pin "B16") (pinfunction "Ground_B16") (pintype "passive"))
      (node (ref "J2") (pin "B18") (pinfunction "Ground_B18") (pintype "passive"))
      (node (ref "J2") (pin "B21") (pinfunction "Ground_B21") (pintype "passive"))
      (node (ref "J2") (pin "B22") (pinfunction "Ground_B22") (pintype "passive"))
      (node (ref "J2") (pin "B25") (pinfunction "Ground_B25") (pintype "passive"))
      (node (ref "J2") (pin "B26") (pinfunction "Ground_B26") (pintype "passive"))
      (node (ref "J2") (pin "B29") (pinfunction "Ground_B29") (pintype "passive"))
      (node (ref "J2") (pin "B32") (pinfunction "Ground_B32") (pintype "passive"))
      (node (ref "J2") (pin "B35") (pinfunction "Ground_B35") (pintype "passive"))
      (node (ref "J2") (pin "B36") (pinfunction "Ground_B36") (pintype "passive"))
      (node (ref "J2") (pin "B39") (pinfunction "Ground_B39") (pintype "passive"))
      (node (ref "J2") (pin "B4") (pinfunction "Ground_B4") (pintype "passive"))
      (node (ref "J2") (pin "B40") (pinfunction "Ground_B40") (pintype "passive"))
      (node (ref "J2") (pin "B43") (pinfunction "Ground_B43") (pintype "passive"))
      (node (ref "J2") (pin "B44") (pinfunction "Ground_B44") (pintype "passive"))
      (node (ref "J2") (pin "B47") (pinfunction "Ground_B47") (pintype "passive"))
      (node (ref "J2") (pin "B49") (pinfunction "Ground_B49") (pintype "passive"))
      (node (ref "J2") (pin "B52") (pinfunction "Ground_B52") (pintype "passive"))
      (node (ref "J2") (pin "B53") (pinfunction "Ground_B53") (pintype "passive"))
      (node (ref "J2") (pin "B56") (pinfunction "Ground_B56") (pintype "passive"))
      (node (ref "J2") (pin "B57") (pinfunction "Ground_B57") (pintype "passive"))
      (node (ref "J2") (pin "B60") (pinfunction "Ground_B60") (pintype "passive"))
      (node (ref "J2") (pin "B61") (pinfunction "Ground_B61") (pintype "passive"))
      (node (ref "J2") (pin "B64") (pinfunction "Ground_B64") (pintype "passive"))
      (node (ref "J2") (pin "B65") (pinfunction "Ground_B65") (pintype "passive"))
      (node (ref "J2") (pin "B68") (pinfunction "Ground_B68") (pintype "passive"))
      (node (ref "J2") (pin "B69") (pinfunction "Ground_B69") (pintype "passive"))
      (node (ref "J2") (pin "B7") (pinfunction "Ground_B7") (pintype "passive"))
      (node (ref "J2") (pin "B72") (pinfunction "Ground_B72") (pintype "passive"))
      (node (ref "J2") (pin "B73") (pinfunction "Ground_B73") (pintype "passive"))
      (node (ref "J2") (pin "B76") (pinfunction "Ground_B76") (pintype "passive"))
      (node (ref "J2") (pin "B77") (pinfunction "Ground_B77") (pintype "passive"))
      (node (ref "J2") (pin "B80") (pinfunction "Ground_B80") (pintype "passive"))
      (node (ref "J3") (pin "A12") (pinfunction "GND_A12") (pintype "passive"))
      (node (ref "J3") (pin "A15") (pinfunction "GND_A15") (pintype "passive"))
      (node (ref "J3") (pin "A18") (pinfunction "GND_A18") (pintype "passive"))
      (node (ref "J3") (pin "A20") (pinfunction "GND_A20") (pintype "passive"))
      (node (ref "J3") (pin "A23") (pinfunction "GND_A23") (pintype "passive"))
      (node (ref "J3") (pin "A24") (pinfunction "GND_A24") (pintype "passive"))
      (node (ref "J3") (pin "A27") (pinfunction "GND_A27") (pintype "passive"))
      (node (ref "J3") (pin "A28") (pinfunction "GND_A28") (pintype "passive"))
      (node (ref "J3") (pin "A31") (pinfunction "GND_A31") (pintype "passive"))
      (node (ref "J3") (pin "A4") (pinfunction "GND_A4") (pintype "passive"))
      (node (ref "J3") (pin "B13") (pinfunction "GND_B13") (pintype "passive"))
      (node (ref "J3") (pin "B16") (pinfunction "GND_B16") (pintype "passive"))
      (node (ref "J3") (pin "B18") (pinfunction "GND_B18") (pintype "passive"))
      (node (ref "J3") (pin "B21") (pinfunction "GND_B21") (pintype "passive"))
      (node (ref "J3") (pin "B22") (pinfunction "GND_B22") (pintype "passive"))
      (node (ref "J3") (pin "B25") (pinfunction "GND_B25") (pintype "passive"))
      (node (ref "J3") (pin "B26") (pinfunction "GND_B26") (pintype "passive"))
      (node (ref "J3") (pin "B29") (pinfunction "GND_B29") (pintype "passive"))
      (node (ref "J3") (pin "B32") (pinfunction "GND_B32") (pintype "passive"))
      (node (ref "J3") (pin "B4") (pinfunction "GND_B4") (pintype "passive"))
      (node (ref "J3") (pin "B7") (pinfunction "GND_B7") (pintype "passive"))
      (node (ref "J4") (pin "A12") (pinfunction "GND_A12") (pintype "passive"))
      (node (ref "J4") (pin "A15") (pinfunction "GND_A15") (pintype "passive"))
      (node (ref "J4") (pin "A18") (pinfunction "GND_A18") (pintype "passive"))
      (node (ref "J4") (pin "A20") (pinfunction "GND_A20") (pintype "passive"))
      (node (ref "J4") (pin "A23") (pinfunction "GND_A23") (pintype "passive"))
      (node (ref "J4") (pin "A24") (pinfunction "GND_A24") (pintype "passive"))
      (node (ref "J4") (pin "A27") (pinfunction "GND_A27") (pintype "passive"))
      (node (ref "J4") (pin "A28") (pinfunction "GND_A28") (pintype "passive"))
      (node (ref "J4") (pin "A31") (pinfunction "GND_A31") (pintype "passive"))
      (node (ref "J4") (pin "A4") (pinfunction "GND_A4") (pintype "passive"))
      (node (ref "J4") (pin "B13") (pinfunction "GND_B13") (pintype "passive"))
      (node (ref "J4") (pin "B16") (pinfunction "GND_B16") (pintype "passive"))
      (node (ref "J4") (pin "B18") (pinfunction "GND_B18") (pintype "passive"))
      (node (ref "J4") (pin "B21") (pinfunction "GND_B21") (pintype "passive"))
      (node (ref "J4") (pin "B22") (pinfunction "GND_B22") (pintype "passive"))
      (node (ref "J4") (pin "B25") (pinfunction "GND_B25") (pintype "passive"))
      (node (ref "J4") (pin "B26") (pinfunction "GND_B26") (pintype "passive"))
      (node (ref "J4") (pin "B29") (pinfunction "GND_B29") (pintype "passive"))
      (node (ref "J4") (pin "B32") (pinfunction "GND_B32") (pintype "passive"))
      (node (ref "J4") (pin "B4") (pinfunction "GND_B4") (pintype "passive"))
      (node (ref "J4") (pin "B7") (pinfunction "GND_B7") (pintype "passive"))
      (node (ref "J5") (pin "A12") (pinfunction "GND_A12") (pintype "passive"))
      (node (ref "J5") (pin "A15") (pinfunction "GND_A15") (pintype "passive"))
      (node (ref "J5") (pin "A18") (pinfunction "GND_A18") (pintype "passive"))
      (node (ref "J5") (pin "A20") (pinfunction "GND_A20") (pintype "passive"))
      (node (ref "J5") (pin "A23") (pinfunction "GND_A23") (pintype "passive"))
      (node (ref "J5") (pin "A24") (pinfunction "GND_A24") (pintype "passive"))
      (node (ref "J5") (pin "A27") (pinfunction "GND_A27") (pintype "passive"))
      (node (ref "J5") (pin "A28") (pinfunction "GND_A28") (pintype "passive"))
      (node (ref "J5") (pin "A31") (pinfunction "GND_A31") (pintype "passive"))
      (node (ref "J5") (pin "A4") (pinfunction "GND_A4") (pintype "passive"))
      (node (ref "J5") (pin "B13") (pinfunction "GND_B13") (pintype "passive"))
      (node (ref "J5") (pin "B16") (pinfunction "GND_B16") (pintype "passive"))
      (node (ref "J5") (pin "B18") (pinfunction "GND_B18") (pintype "passive"))
      (node (ref "J5") (pin "B21") (pinfunction "GND_B21") (pintype "passive"))
      (node (ref "J5") (pin "B22") (pinfunction "GND_B22") (pintype "passive"))
      (node (ref "J5") (pin "B25") (pinfunction "GND_B25") (pintype "passive"))
      (node (ref "J5") (pin "B26") (pinfunction "GND_B26") (pintype "passive"))
      (node (ref "J5") (pin "B29") (pinfunction "GND_B29") (pintype "passive"))
      (node (ref "J5") (pin "B32") (pinfunction "GND_B32") (pintype "passive"))
      (node (ref "J5") (pin "B4") (pinfunction "GND_B4") (pintype "passive"))
      (node (ref "J5") (pin "B7") (pinfunction "GND_B7") (pintype "passive"))
      (node (ref "JP1") (pin "21") (pinfunction "21_21") (pintype "passive"))
      (node (ref "JP1") (pin "22") (pinfunction "22_22") (pintype "passive"))
      (node (ref "JP1") (pin "23") (pinfunction "23_23") (pintype "passive"))
      (node (ref "JP1") (pin "24") (pinfunction "24_24") (pintype "passive"))
      (node (ref "JP2") (pin "17") (pinfunction "17_17") (pintype "passive"))
      (node (ref "JP2") (pin "18") (pinfunction "18_18") (pintype "passive"))
      (node (ref "JP2") (pin "19") (pinfunction "19_19") (pintype "passive"))
      (node (ref "JP2") (pin "20") (pinfunction "20_20") (pintype "passive"))
      (node (ref "JP3") (pin "17") (pinfunction "17_17") (pintype "passive"))
      (node (ref "JP3") (pin "18") (pinfunction "18_18") (pintype "passive"))
      (node (ref "JP3") (pin "19") (pinfunction "19_19") (pintype "passive"))
      (node (ref "JP3") (pin "20") (pinfunction "20_20") (pintype "passive"))
      (node (ref "JP4") (pin "17") (pinfunction "17_17") (pintype "passive"))
      (node (ref "JP4") (pin "18") (pinfunction "18_18") (pintype "passive"))
      (node (ref "JP4") (pin "19") (pinfunction "19_19") (pintype "passive"))
      (node (ref "JP4") (pin "20") (pinfunction "20_20") (pintype "passive"))
      (node (ref "R10") (pin "2") (pinfunction "2_2") (pintype "passive"))
      (node (ref "R11") (pin "2") (pinfunction "2_2") (pintype "passive"))
      (node (ref "R12") (pin "2") (pinfunction "2_2") (pintype "passive"))
      (node (ref "R13") (pin "2") (pinfunction "2_2") (pintype "passive"))
      (node (ref "R14") (pin "2") (pinfunction "2_2") (pintype "passive"))
      (node (ref "R15") (pin "2") (pinfunction "2_2") (pintype "passive"))
      (node (ref "R16") (pin "2") (pinfunction "2_2") (pintype "passive"))
      (node (ref "R17") (pin "1") (pinfunction "1_1") (pintype "passive"))
      (node (ref "R18") (pin "2") (pinfunction "2_2") (pintype "passive"))
      (node (ref "R19") (pin "2") (pinfunction "2_2") (pintype "passive"))
      (node (ref "R9") (pin "2") (pinfunction "2_2") (pintype "passive"))
      (node (ref "U1") (pin "1") (pinfunction "GND_1") (pintype "passive"))
      (node (ref "U1") (pin "13") (pinfunction "CLKIN_SEL0_13") (pintype "passive"))
      (node (ref "U1") (pin "16") (pinfunction "CLKIN_SEL1_16") (pintype "passive"))
      (node (ref "U1") (pin "17") (pinfunction "GND_17") (pintype "passive"))
      (node (ref "U1") (pin "24") (pinfunction "GND_24") (pintype "passive"))
      (node (ref "U1") (pin "31") (pinfunction "REFOUT_EN_31") (pintype "passive"))
      (node (ref "U1") (pin "33") (pinfunction "_EP_33") (pintype "passive"))
      (node (ref "U1") (pin "8") (pinfunction "GND_8") (pintype "passive"))
      (node (ref "U1") (pin "9") (pinfunction "CLKOUT_EN_9") (pintype "passive"))
    )
    (net (code "105") (name "Net-(J2-CLKREQ#)") (class "Default")
      (node (ref "J2") (pin "B12") (pinfunction "CLKREQ#_B12") (pintype "passive"))
      (node (ref "R18") (pin "1") (pinfunction "1_1") (pintype "passive"))
    )
    (net (code "106") (name "Net-(J2-PRSNT1#)") (class "Default")
      (node (ref "J2") (pin "A1") (pinfunction "PRSNT1#_A1") (pintype "passive"))
      (node (ref "R17") (pin "2") (pinfunction "2_2") (pintype "passive"))
    )
    (net (code "107") (name "Net-(J2-PRSNT2#-PadB81)") (class "Default")
      (node (ref "J2") (pin "B81") (pinfunction "PRSNT2#_B81") (pintype "passive"))
      (node (ref "R19") (pin "1") (pinfunction "1_1") (pintype "passive"))
    )
    (net (code "108") (name "VCC3.3V-A") (class "Default")
      (node (ref "J4") (pin "A10") (pinfunction "+3.3V_A10") (pintype "passive"))
      (node (ref "J4") (pin "A9") (pinfunction "+3.3V_A9") (pintype "passive"))
      (node (ref "J4") (pin "B8") (pinfunction "+3.3V_B8") (pintype "passive"))
    )
    (net (code "109") (name "VCC3.3V-B") (class "Default")
      (node (ref "J5") (pin "A10") (pinfunction "+3.3V_A10") (pintype "passive"))
      (node (ref "J5") (pin "A9") (pinfunction "+3.3V_A9") (pintype "passive"))
      (node (ref "J5") (pin "B8") (pinfunction "+3.3V_B8") (pintype "passive"))
    )
    (net (code "110") (name "VCC3.3V-C") (class "Default")
      (node (ref "J3") (pin "A10") (pinfunction "+3.3V_A10") (pintype "passive"))
      (node (ref "J3") (pin "A9") (pinfunction "+3.3V_A9") (pintype "passive"))
      (node (ref "J3") (pin "B8") (pinfunction "+3.3V_B8") (pintype "passive"))
    )
    (net (code "111") (name "VCC3V3") (class "Default")
      (node (ref "C1") (pin "2") (pinfunction "2_2") (pintype "passive"))
      (node (ref "C2") (pin "2") (pinfunction "2_2") (pintype "passive"))
      (node (ref "C3") (pin "2") (pinfunction "2_2") (pintype "passive"))
      (node (ref "C4") (pin "2") (pinfunction "2_2") (pintype "passive"))
      (node (ref "C5") (pin "2") (pinfunction "2_2") (pintype "passive"))
      (node (ref "C6") (pin "2") (pinfunction "2_2") (pintype "passive"))
      (node (ref "C7") (pin "2") (pinfunction "2_2") (pintype "passive"))
      (node (ref "C8") (pin "2") (pinfunction "2_2") (pintype "passive"))
      (node (ref "U1") (pin "10") (pinfunction "VCC_10") (pintype "passive"))
      (node (ref "U1") (pin "2") (pinfunction "VCCOA_2") (pintype "passive"))
      (node (ref "U1") (pin "20") (pinfunction "VCCOB_20") (pintype "passive"))
      (node (ref "U1") (pin "23") (pinfunction "VCCOB_23") (pintype "passive"))
      (node (ref "U1") (pin "28") (pinfunction "VCC_28") (pintype "passive"))
      (node (ref "U1") (pin "30") (pinfunction "VCCOC_30") (pintype "passive"))
      (node (ref "U1") (pin "32") (pinfunction "VCC_32") (pintype "passive"))
      (node (ref "U1") (pin "5") (pinfunction "VCCOA_5") (pintype "passive"))
    )
    (net (code "112") (name "VCC12V") (class "Default")
      (node (ref "J2") (pin "A2") (pinfunction "+12V_A2") (pintype "passive"))
      (node (ref "J2") (pin "A3") (pinfunction "+12V_A3") (pintype "passive"))
      (node (ref "J2") (pin "B1") (pinfunction "+12V_B1") (pintype "passive"))
      (node (ref "J2") (pin "B2") (pinfunction "+12V_B2") (pintype "passive"))
      (node (ref "J2") (pin "B3") (pinfunction "+12V_B3") (pintype "passive"))
    )
    (net (code "113") (name "unconnected-(J1-BP_TYPE-PadB9)") (class "Default")
      (node (ref "J1") (pin "B9") (pinfunction "BP_TYPE_B9") (pintype "passive"))
    )
    (net (code "114") (name "unconnected-(J1-CPRSNT#-PadA13)") (class "Default")
      (node (ref "J1") (pin "A13") (pinfunction "CPRSNT#_A13") (pintype "passive"))
    )
    (net (code "115") (name "unconnected-(J1-CWAKE#-PadB10)") (class "Default")
      (node (ref "J1") (pin "B10") (pinfunction "CWAKE#_B10") (pintype "passive"))
    )
    (net (code "116") (name "unconnected-(J1-PERN0-PadB4)") (class "Default")
      (node (ref "J1") (pin "B4") (pinfunction "PERN0_B4") (pintype "passive"))
    )
    (net (code "117") (name "unconnected-(J1-PERN1-PadB7)") (class "Default")
      (node (ref "J1") (pin "B7") (pinfunction "PERN1_B7") (pintype "passive"))
    )
    (net (code "118") (name "unconnected-(J1-PERN2-PadB16)") (class "Default")
      (node (ref "J1") (pin "B16") (pinfunction "PERN2_B16") (pintype "passive"))
    )
    (net (code "119") (name "unconnected-(J1-PERN3-PadB19)") (class "Default")
      (node (ref "J1") (pin "B19") (pinfunction "PERN3_B19") (pintype "passive"))
    )
    (net (code "120") (name "unconnected-(J1-PERP0-PadB3)") (class "Default")
      (node (ref "J1") (pin "B3") (pinfunction "PERP0_B3") (pintype "passive"))
    )
    (net (code "121") (name "unconnected-(J1-PERP1-PadB6)") (class "Default")
      (node (ref "J1") (pin "B6") (pinfunction "PERP1_B6") (pintype "passive"))
    )
    (net (code "122") (name "unconnected-(J1-PERP2-PadB15)") (class "Default")
      (node (ref "J1") (pin "B15") (pinfunction "PERP2_B15") (pintype "passive"))
    )
    (net (code "123") (name "unconnected-(J1-PERP3-PadB18)") (class "Default")
      (node (ref "J1") (pin "B18") (pinfunction "PERP3_B18") (pintype "passive"))
    )
    (net (code "124") (name "unconnected-(J1-PERST#-PadA12)") (class "Default")
      (node (ref "J1") (pin "A12") (pinfunction "PERST#_A12") (pintype "passive"))
    )
    (net (code "125") (name "unconnected-(J1-PETN0-PadA4)") (class "Default")
      (node (ref "J1") (pin "A4") (pinfunction "PETN0_A4") (pintype "passive"))
    )
    (net (code "126") (name "unconnected-(J1-PETN1-PadA7)") (class "Default")
      (node (ref "J1") (pin "A7") (pinfunction "PETN1_A7") (pintype "passive"))
    )
    (net (code "127") (name "unconnected-(J1-PETN2-PadA16)") (class "Default")
      (node (ref "J1") (pin "A16") (pinfunction "PETN2_A16") (pintype "passive"))
    )
    (net (code "128") (name "unconnected-(J1-PETN3-PadA19)") (class "Default")
      (node (ref "J1") (pin "A19") (pinfunction "PETN3_A19") (pintype "passive"))
    )
    (net (code "129") (name "unconnected-(J1-PETP0-PadA3)") (class "Default")
      (node (ref "J1") (pin "A3") (pinfunction "PETP0_A3") (pintype "passive"))
    )
    (net (code "130") (name "unconnected-(J1-PETP1-PadA6)") (class "Default")
      (node (ref "J1") (pin "A6") (pinfunction "PETP1_A6") (pintype "passive"))
    )
    (net (code "131") (name "unconnected-(J1-PETP2-PadA15)") (class "Default")
      (node (ref "J1") (pin "A15") (pinfunction "PETP2_A15") (pintype "passive"))
    )
    (net (code "132") (name "unconnected-(J1-PETP3-PadA18)") (class "Default")
      (node (ref "J1") (pin "A18") (pinfunction "PETP3_A18") (pintype "passive"))
    )
    (net (code "133") (name "unconnected-(J1-POWER-PadA21)") (class "Default")
      (node (ref "J1") (pin "A21") (pinfunction "POWER_A21") (pintype "passive"))
    )
    (net (code "134") (name "unconnected-(J1-POWER-PadB1)") (class "Default")
      (node (ref "J1") (pin "B1") (pinfunction "POWER_B1") (pintype "passive"))
    )
    (net (code "135") (name "unconnected-(J1-REFCLK+-PadB12)") (class "Default")
      (node (ref "J1") (pin "B12") (pinfunction "REFCLK+_B12") (pintype "passive"))
    )
    (net (code "136") (name "unconnected-(J1-REFCLK--PadB13)") (class "Default")
      (node (ref "J1") (pin "B13") (pinfunction "REFCLK-_B13") (pintype "passive"))
    )
    (net (code "137") (name "unconnected-(J1-RESERVED-PadA1)") (class "Default")
      (node (ref "J1") (pin "A1") (pinfunction "RESERVED_A1") (pintype "passive"))
    )
    (net (code "138") (name "unconnected-(J1-RESERVED-PadB21)") (class "Default")
      (node (ref "J1") (pin "B21") (pinfunction "RESERVED_B21") (pintype "passive"))
    )
    (net (code "139") (name "unconnected-(J1-SMDAT-PadA10)") (class "Default")
      (node (ref "J1") (pin "A10") (pinfunction "SMDAT_A10") (pintype "passive"))
    )
    (net (code "140") (name "unconnected-(J1-SMSCK-PadA9)") (class "Default")
      (node (ref "J1") (pin "A9") (pinfunction "SMSCK_A9") (pintype "passive"))
    )
    (net (code "141") (name "unconnected-(J2-+3.3V-PadA9)") (class "Default")
      (node (ref "J2") (pin "A9") (pinfunction "+3.3V_A9") (pintype "passive"))
    )
    (net (code "142") (name "unconnected-(J2-+3.3V-PadA10)") (class "Default")
      (node (ref "J2") (pin "A10") (pinfunction "+3.3V_A10") (pintype "passive"))
    )
    (net (code "143") (name "unconnected-(J2-+3.3V-PadB8)") (class "Default")
      (node (ref "J2") (pin "B8") (pinfunction "+3.3V_B8") (pintype "passive"))
    )
    (net (code "144") (name "unconnected-(J2-+3.3Vaux-PadB10)") (class "Default")
      (node (ref "J2") (pin "B10") (pinfunction "+3.3Vaux_B10") (pintype "passive"))
    )
    (net (code "145") (name "unconnected-(J2-JTAG1-PadB9)") (class "Default")
      (node (ref "J2") (pin "B9") (pinfunction "JTAG1_B9") (pintype "passive"))
    )
    (net (code "146") (name "unconnected-(J2-JTAG2-PadA5)") (class "Default")
      (node (ref "J2") (pin "A5") (pinfunction "JTAG2_A5") (pintype "passive"))
    )
    (net (code "147") (name "unconnected-(J2-JTAG3-PadA6)") (class "Default")
      (node (ref "J2") (pin "A6") (pinfunction "JTAG3_A6") (pintype "passive"))
    )
    (net (code "148") (name "unconnected-(J2-JTAG4-PadA7)") (class "Default")
      (node (ref "J2") (pin "A7") (pinfunction "JTAG4_A7") (pintype "passive"))
    )
    (net (code "149") (name "unconnected-(J2-JTAG5-PadA8)") (class "Default")
      (node (ref "J2") (pin "A8") (pinfunction "JTAG5_A8") (pintype "passive"))
    )
    (net (code "150") (name "unconnected-(J2-PRSNT2#-PadB17)") (class "Default")
      (node (ref "J2") (pin "B17") (pinfunction "PRSNT2#_B17") (pintype "passive"))
    )
    (net (code "151") (name "unconnected-(J2-PRSNT2#-PadB31)") (class "Default")
      (node (ref "J2") (pin "B31") (pinfunction "PRSNT2#_B31") (pintype "passive"))
    )
    (net (code "152") (name "unconnected-(J2-PRSNT2#-PadB48)") (class "Default")
      (node (ref "J2") (pin "B48") (pinfunction "PRSNT2#_B48") (pintype "passive"))
    )
    (net (code "153") (name "unconnected-(J2-PWRBRK#-PadB30)") (class "Default")
      (node (ref "J2") (pin "B30") (pinfunction "PWRBRK#_B30") (pintype "passive"))
    )
    (net (code "154") (name "unconnected-(J2-RVSD-PadA19)") (class "Default")
      (node (ref "J2") (pin "A19") (pinfunction "RVSD_A19") (pintype "passive"))
    )
    (net (code "155") (name "unconnected-(J2-RVSD-PadA32)") (class "Default")
      (node (ref "J2") (pin "A32") (pinfunction "RVSD_A32") (pintype "passive"))
    )
    (net (code "156") (name "unconnected-(J2-RVSD-PadA33)") (class "Default")
      (node (ref "J2") (pin "A33") (pinfunction "RVSD_A33") (pintype "passive"))
    )
    (net (code "157") (name "unconnected-(J2-RVSD-PadA50)") (class "Default")
      (node (ref "J2") (pin "A50") (pinfunction "RVSD_A50") (pintype "passive"))
    )
    (net (code "158") (name "unconnected-(J2-RVSD-PadB82)") (class "Default")
      (node (ref "J2") (pin "B82") (pinfunction "RVSD_B82") (pintype "passive"))
    )
    (net (code "159") (name "unconnected-(J2-SMBCLK-PadB5)") (class "Default")
      (node (ref "J2") (pin "B5") (pinfunction "SMBCLK_B5") (pintype "passive"))
    )
    (net (code "160") (name "unconnected-(J2-SMBDAT-PadB6)") (class "Default")
      (node (ref "J2") (pin "B6") (pinfunction "SMBDAT_B6") (pintype "passive"))
    )
    (net (code "161") (name "unconnected-(J2-WAKE#-PadB11)") (class "Default")
      (node (ref "J2") (pin "B11") (pinfunction "WAKE#_B11") (pintype "passive"))
    )
    (net (code "162") (name "unconnected-(J3-+12V-PadA2)") (class "Default")
      (node (ref "J3") (pin "A2") (pinfunction "+12V_A2") (pintype "passive"))
    )
    (net (code "163") (name "unconnected-(J3-+12V-PadA3)") (class "Default")
      (node (ref "J3") (pin "A3") (pinfunction "+12V_A3") (pintype "passive"))
    )
    (net (code "164") (name "unconnected-(J3-+12V-PadB1)") (class "Default")
      (node (ref "J3") (pin "B1") (pinfunction "+12V_B1") (pintype "passive"))
    )
    (net (code "165") (name "unconnected-(J3-+12V-PadB2)") (class "Default")
      (node (ref "J3") (pin "B2") (pinfunction "+12V_B2") (pintype "passive"))
    )
    (net (code "166") (name "unconnected-(J3-+12V-PadB3)") (class "Default")
      (node (ref "J3") (pin "B3") (pinfunction "+12V_B3") (pintype "passive"))
    )
    (net (code "167") (name "unconnected-(J3-3.3Vaux-PadB10)") (class "Default")
      (node (ref "J3") (pin "B10") (pinfunction "3.3Vaux_B10") (pintype "passive"))
    )
    (net (code "168") (name "unconnected-(J3-GND-PadSH1)") (class "Default")
      (node (ref "J3") (pin "SH1") (pinfunction "GND_SH1") (pintype "passive"))
    )
    (net (code "169") (name "unconnected-(J3-GND-PadSH2)") (class "Default")
      (node (ref "J3") (pin "SH2") (pinfunction "GND_SH2") (pintype "passive"))
    )
    (net (code "170") (name "unconnected-(J3-JTAG1-PadB9)") (class "Default")
      (node (ref "J3") (pin "B9") (pinfunction "JTAG1_B9") (pintype "passive"))
    )
    (net (code "171") (name "unconnected-(J3-JTAG2-PadA5)") (class "Default")
      (node (ref "J3") (pin "A5") (pinfunction "JTAG2_A5") (pintype "passive"))
    )
    (net (code "172") (name "unconnected-(J3-JTAG3-PadA6)") (class "Default")
      (node (ref "J3") (pin "A6") (pinfunction "JTAG3_A6") (pintype "passive"))
    )
    (net (code "173") (name "unconnected-(J3-JTAG4-PadA7)") (class "Default")
      (node (ref "J3") (pin "A7") (pinfunction "JTAG4_A7") (pintype "passive"))
    )
    (net (code "174") (name "unconnected-(J3-JTAG5-PadA8)") (class "Default")
      (node (ref "J3") (pin "A8") (pinfunction "JTAG5_A8") (pintype "passive"))
    )
    (net (code "175") (name "unconnected-(J3-PRSNT1-PadA1)") (class "Default")
      (node (ref "J3") (pin "A1") (pinfunction "PRSNT1_A1") (pintype "passive"))
    )
    (net (code "176") (name "unconnected-(J3-PRSNT2-PadB17)") (class "Default")
      (node (ref "J3") (pin "B17") (pinfunction "PRSNT2_B17") (pintype "passive"))
    )
    (net (code "177") (name "unconnected-(J3-PRSNT2-PadB31)") (class "Default")
      (node (ref "J3") (pin "B31") (pinfunction "PRSNT2_B31") (pintype "passive"))
    )
    (net (code "178") (name "unconnected-(J3-RSVD-PadA19)") (class "Default")
      (node (ref "J3") (pin "A19") (pinfunction "RSVD_A19") (pintype "passive"))
    )
    (net (code "179") (name "unconnected-(J3-RSVD-PadA32)") (class "Default")
      (node (ref "J3") (pin "A32") (pinfunction "RSVD_A32") (pintype "passive"))
    )
    (net (code "180") (name "unconnected-(J3-RSVD-PadB30)") (class "Default")
      (node (ref "J3") (pin "B30") (pinfunction "RSVD_B30") (pintype "passive"))
    )
    (net (code "181") (name "unconnected-(J3-SBCLK-PadB5)") (class "Default")
      (node (ref "J3") (pin "B5") (pinfunction "SBCLK_B5") (pintype "passive"))
    )
    (net (code "182") (name "unconnected-(J3-SMDAT-PadB6)") (class "Default")
      (node (ref "J3") (pin "B6") (pinfunction "SMDAT_B6") (pintype "passive"))
    )
    (net (code "183") (name "unconnected-(J3-WAKE#-PadB11)") (class "Default")
      (node (ref "J3") (pin "B11") (pinfunction "WAKE#_B11") (pintype "passive"))
    )
    (net (code "184") (name "unconnected-(J4-+12V-PadA2)") (class "Default")
      (node (ref "J4") (pin "A2") (pinfunction "+12V_A2") (pintype "passive"))
    )
    (net (code "185") (name "unconnected-(J4-+12V-PadA3)") (class "Default")
      (node (ref "J4") (pin "A3") (pinfunction "+12V_A3") (pintype "passive"))
    )
    (net (code "186") (name "unconnected-(J4-+12V-PadB1)") (class "Default")
      (node (ref "J4") (pin "B1") (pinfunction "+12V_B1") (pintype "passive"))
    )
    (net (code "187") (name "unconnected-(J4-+12V-PadB2)") (class "Default")
      (node (ref "J4") (pin "B2") (pinfunction "+12V_B2") (pintype "passive"))
    )
    (net (code "188") (name "unconnected-(J4-+12V-PadB3)") (class "Default")
      (node (ref "J4") (pin "B3") (pinfunction "+12V_B3") (pintype "passive"))
    )
    (net (code "189") (name "unconnected-(J4-3.3Vaux-PadB10)") (class "Default")
      (node (ref "J4") (pin "B10") (pinfunction "3.3Vaux_B10") (pintype "passive"))
    )
    (net (code "190") (name "unconnected-(J4-GND-PadSH1)") (class "Default")
      (node (ref "J4") (pin "SH1") (pinfunction "GND_SH1") (pintype "passive"))
    )
    (net (code "191") (name "unconnected-(J4-GND-PadSH2)") (class "Default")
      (node (ref "J4") (pin "SH2") (pinfunction "GND_SH2") (pintype "passive"))
    )
    (net (code "192") (name "unconnected-(J4-JTAG1-PadB9)") (class "Default")
      (node (ref "J4") (pin "B9") (pinfunction "JTAG1_B9") (pintype "passive"))
    )
    (net (code "193") (name "unconnected-(J4-JTAG2-PadA5)") (class "Default")
      (node (ref "J4") (pin "A5") (pinfunction "JTAG2_A5") (pintype "passive"))
    )
    (net (code "194") (name "unconnected-(J4-JTAG3-PadA6)") (class "Default")
      (node (ref "J4") (pin "A6") (pinfunction "JTAG3_A6") (pintype "passive"))
    )
    (net (code "195") (name "unconnected-(J4-JTAG4-PadA7)") (class "Default")
      (node (ref "J4") (pin "A7") (pinfunction "JTAG4_A7") (pintype "passive"))
    )
    (net (code "196") (name "unconnected-(J4-JTAG5-PadA8)") (class "Default")
      (node (ref "J4") (pin "A8") (pinfunction "JTAG5_A8") (pintype "passive"))
    )
    (net (code "197") (name "unconnected-(J4-PRSNT1-PadA1)") (class "Default")
      (node (ref "J4") (pin "A1") (pinfunction "PRSNT1_A1") (pintype "passive"))
    )
    (net (code "198") (name "unconnected-(J4-PRSNT2-PadB17)") (class "Default")
      (node (ref "J4") (pin "B17") (pinfunction "PRSNT2_B17") (pintype "passive"))
    )
    (net (code "199") (name "unconnected-(J4-PRSNT2-PadB31)") (class "Default")
      (node (ref "J4") (pin "B31") (pinfunction "PRSNT2_B31") (pintype "passive"))
    )
    (net (code "200") (name "unconnected-(J4-RSVD-PadA19)") (class "Default")
      (node (ref "J4") (pin "A19") (pinfunction "RSVD_A19") (pintype "passive"))
    )
    (net (code "201") (name "unconnected-(J4-RSVD-PadA32)") (class "Default")
      (node (ref "J4") (pin "A32") (pinfunction "RSVD_A32") (pintype "passive"))
    )
    (net (code "202") (name "unconnected-(J4-RSVD-PadB12)") (class "Default")
      (node (ref "J4") (pin "B12") (pinfunction "RSVD_B12") (pintype "passive"))
    )
    (net (code "203") (name "unconnected-(J4-RSVD-PadB30)") (class "Default")
      (node (ref "J4") (pin "B30") (pinfunction "RSVD_B30") (pintype "passive"))
    )
    (net (code "204") (name "unconnected-(J4-SBCLK-PadB5)") (class "Default")
      (node (ref "J4") (pin "B5") (pinfunction "SBCLK_B5") (pintype "passive"))
    )
    (net (code "205") (name "unconnected-(J4-SMDAT-PadB6)") (class "Default")
      (node (ref "J4") (pin "B6") (pinfunction "SMDAT_B6") (pintype "passive"))
    )
    (net (code "206") (name "unconnected-(J4-WAKE#-PadB11)") (class "Default")
      (node (ref "J4") (pin "B11") (pinfunction "WAKE#_B11") (pintype "passive"))
    )
    (net (code "207") (name "unconnected-(J5-+12V-PadA2)") (class "Default")
      (node (ref "J5") (pin "A2") (pinfunction "+12V_A2") (pintype "passive"))
    )
    (net (code "208") (name "unconnected-(J5-+12V-PadA3)") (class "Default")
      (node (ref "J5") (pin "A3") (pinfunction "+12V_A3") (pintype "passive"))
    )
    (net (code "209") (name "unconnected-(J5-+12V-PadB1)") (class "Default")
      (node (ref "J5") (pin "B1") (pinfunction "+12V_B1") (pintype "passive"))
    )
    (net (code "210") (name "unconnected-(J5-+12V-PadB2)") (class "Default")
      (node (ref "J5") (pin "B2") (pinfunction "+12V_B2") (pintype "passive"))
    )
    (net (code "211") (name "unconnected-(J5-+12V-PadB3)") (class "Default")
      (node (ref "J5") (pin "B3") (pinfunction "+12V_B3") (pintype "passive"))
    )
    (net (code "212") (name "unconnected-(J5-3.3Vaux-PadB10)") (class "Default")
      (node (ref "J5") (pin "B10") (pinfunction "3.3Vaux_B10") (pintype "passive"))
    )
    (net (code "213") (name "unconnected-(J5-GND-PadSH1)") (class "Default")
      (node (ref "J5") (pin "SH1") (pinfunction "GND_SH1") (pintype "passive"))
    )
    (net (code "214") (name "unconnected-(J5-GND-PadSH2)") (class "Default")
      (node (ref "J5") (pin "SH2") (pinfunction "GND_SH2") (pintype "passive"))
    )
    (net (code "215") (name "unconnected-(J5-JTAG1-PadB9)") (class "Default")
      (node (ref "J5") (pin "B9") (pinfunction "JTAG1_B9") (pintype "passive"))
    )
    (net (code "216") (name "unconnected-(J5-JTAG2-PadA5)") (class "Default")
      (node (ref "J5") (pin "A5") (pinfunction "JTAG2_A5") (pintype "passive"))
    )
    (net (code "217") (name "unconnected-(J5-JTAG3-PadA6)") (class "Default")
      (node (ref "J5") (pin "A6") (pinfunction "JTAG3_A6") (pintype "passive"))
    )
    (net (code "218") (name "unconnected-(J5-JTAG4-PadA7)") (class "Default")
      (node (ref "J5") (pin "A7") (pinfunction "JTAG4_A7") (pintype "passive"))
    )
    (net (code "219") (name "unconnected-(J5-JTAG5-PadA8)") (class "Default")
      (node (ref "J5") (pin "A8") (pinfunction "JTAG5_A8") (pintype "passive"))
    )
    (net (code "220") (name "unconnected-(J5-PRSNT1-PadA1)") (class "Default")
      (node (ref "J5") (pin "A1") (pinfunction "PRSNT1_A1") (pintype "passive"))
    )
    (net (code "221") (name "unconnected-(J5-PRSNT2-PadB17)") (class "Default")
      (node (ref "J5") (pin "B17") (pinfunction "PRSNT2_B17") (pintype "passive"))
    )
    (net (code "222") (name "unconnected-(J5-PRSNT2-PadB31)") (class "Default")
      (node (ref "J5") (pin "B31") (pinfunction "PRSNT2_B31") (pintype "passive"))
    )
    (net (code "223") (name "unconnected-(J5-RSVD-PadA19)") (class "Default")
      (node (ref "J5") (pin "A19") (pinfunction "RSVD_A19") (pintype "passive"))
    )
    (net (code "224") (name "unconnected-(J5-RSVD-PadA32)") (class "Default")
      (node (ref "J5") (pin "A32") (pinfunction "RSVD_A32") (pintype "passive"))
    )
    (net (code "225") (name "unconnected-(J5-RSVD-PadB12)") (class "Default")
      (node (ref "J5") (pin "B12") (pinfunction "RSVD_B12") (pintype "passive"))
    )
    (net (code "226") (name "unconnected-(J5-RSVD-PadB30)") (class "Default")
      (node (ref "J5") (pin "B30") (pinfunction "RSVD_B30") (pintype "passive"))
    )
    (net (code "227") (name "unconnected-(J5-SBCLK-PadB5)") (class "Default")
      (node (ref "J5") (pin "B5") (pinfunction "SBCLK_B5") (pintype "passive"))
    )
    (net (code "228") (name "unconnected-(J5-SMDAT-PadB6)") (class "Default")
      (node (ref "J5") (pin "B6") (pinfunction "SMDAT_B6") (pintype "passive"))
    )
    (net (code "229") (name "unconnected-(J5-WAKE#-PadB11)") (class "Default")
      (node (ref "J5") (pin "B11") (pinfunction "WAKE#_B11") (pintype "passive"))
    )
    (net (code "230") (name "unconnected-(JP2-Pad1)") (class "Default")
      (node (ref "JP2") (pin "1") (pinfunction "1_1") (pintype "passive"))
    )
    (net (code "231") (name "unconnected-(JP2-Pad2)") (class "Default")
      (node (ref "JP2") (pin "2") (pinfunction "2_2") (pintype "passive"))
    )
    (net (code "232") (name "unconnected-(JP2-Pad3)") (class "Default")
      (node (ref "JP2") (pin "3") (pinfunction "3_3") (pintype "passive"))
    )
    (net (code "233") (name "unconnected-(JP2-Pad4)") (class "Default")
      (node (ref "JP2") (pin "4") (pinfunction "4_4") (pintype "passive"))
    )
    (net (code "234") (name "unconnected-(JP2-Pad5)") (class "Default")
      (node (ref "JP2") (pin "5") (pinfunction "5_5") (pintype "passive"))
    )
    (net (code "235") (name "unconnected-(JP2-Pad6)") (class "Default")
      (node (ref "JP2") (pin "6") (pinfunction "6_6") (pintype "passive"))
    )
    (net (code "236") (name "unconnected-(JP2-Pad7)") (class "Default")
      (node (ref "JP2") (pin "7") (pinfunction "7_7") (pintype "passive"))
    )
    (net (code "237") (name "unconnected-(JP2-Pad8)") (class "Default")
      (node (ref "JP2") (pin "8") (pinfunction "8_8") (pintype "passive"))
    )
    (net (code "238") (name "unconnected-(JP2-Pad9)") (class "Default")
      (node (ref "JP2") (pin "9") (pinfunction "9_9") (pintype "passive"))
    )
    (net (code "239") (name "unconnected-(JP2-Pad10)") (class "Default")
      (node (ref "JP2") (pin "10") (pinfunction "10_10") (pintype "passive"))
    )
    (net (code "240") (name "unconnected-(JP2-Pad11)") (class "Default")
      (node (ref "JP2") (pin "11") (pinfunction "11_11") (pintype "passive"))
    )
    (net (code "241") (name "unconnected-(JP2-Pad12)") (class "Default")
      (node (ref "JP2") (pin "12") (pinfunction "12_12") (pintype "passive"))
    )
    (net (code "242") (name "unconnected-(JP2-Pad13)") (class "Default")
      (node (ref "JP2") (pin "13") (pinfunction "13_13") (pintype "passive"))
    )
    (net (code "243") (name "unconnected-(JP2-Pad14)") (class "Default")
      (node (ref "JP2") (pin "14") (pinfunction "14_14") (pintype "passive"))
    )
    (net (code "244") (name "unconnected-(JP2-Pad15)") (class "Default")
      (node (ref "JP2") (pin "15") (pinfunction "15_15") (pintype "passive"))
    )
    (net (code "245") (name "unconnected-(JP2-Pad16)") (class "Default")
      (node (ref "JP2") (pin "16") (pinfunction "16_16") (pintype "passive"))
    )
    (net (code "246") (name "unconnected-(JP3-Pad1)") (class "Default")
      (node (ref "JP3") (pin "1") (pinfunction "1_1") (pintype "passive"))
    )
    (net (code "247") (name "unconnected-(JP3-Pad2)") (class "Default")
      (node (ref "JP3") (pin "2") (pinfunction "2_2") (pintype "passive"))
    )
    (net (code "248") (name "unconnected-(JP3-Pad3)") (class "Default")
      (node (ref "JP3") (pin "3") (pinfunction "3_3") (pintype "passive"))
    )
    (net (code "249") (name "unconnected-(JP3-Pad4)") (class "Default")
      (node (ref "JP3") (pin "4") (pinfunction "4_4") (pintype "passive"))
    )
    (net (code "250") (name "unconnected-(JP3-Pad5)") (class "Default")
      (node (ref "JP3") (pin "5") (pinfunction "5_5") (pintype "passive"))
    )
    (net (code "251") (name "unconnected-(JP3-Pad6)") (class "Default")
      (node (ref "JP3") (pin "6") (pinfunction "6_6") (pintype "passive"))
    )
    (net (code "252") (name "unconnected-(JP3-Pad7)") (class "Default")
      (node (ref "JP3") (pin "7") (pinfunction "7_7") (pintype "passive"))
    )
    (net (code "253") (name "unconnected-(JP3-Pad8)") (class "Default")
      (node (ref "JP3") (pin "8") (pinfunction "8_8") (pintype "passive"))
    )
    (net (code "254") (name "unconnected-(JP3-Pad9)") (class "Default")
      (node (ref "JP3") (pin "9") (pinfunction "9_9") (pintype "passive"))
    )
    (net (code "255") (name "unconnected-(JP3-Pad10)") (class "Default")
      (node (ref "JP3") (pin "10") (pinfunction "10_10") (pintype "passive"))
    )
    (net (code "256") (name "unconnected-(JP3-Pad11)") (class "Default")
      (node (ref "JP3") (pin "11") (pinfunction "11_11") (pintype "passive"))
    )
    (net (code "257") (name "unconnected-(JP3-Pad12)") (class "Default")
      (node (ref "JP3") (pin "12") (pinfunction "12_12") (pintype "passive"))
    )
    (net (code "258") (name "unconnected-(JP3-Pad13)") (class "Default")
      (node (ref "JP3") (pin "13") (pinfunction "13_13") (pintype "passive"))
    )
    (net (code "259") (name "unconnected-(JP3-Pad14)") (class "Default")
      (node (ref "JP3") (pin "14") (pinfunction "14_14") (pintype "passive"))
    )
    (net (code "260") (name "unconnected-(JP3-Pad15)") (class "Default")
      (node (ref "JP3") (pin "15") (pinfunction "15_15") (pintype "passive"))
    )
    (net (code "261") (name "unconnected-(JP3-Pad16)") (class "Default")
      (node (ref "JP3") (pin "16") (pinfunction "16_16") (pintype "passive"))
    )
    (net (code "262") (name "unconnected-(JP4-Pad1)") (class "Default")
      (node (ref "JP4") (pin "1") (pinfunction "1_1") (pintype "passive"))
    )
    (net (code "263") (name "unconnected-(JP4-Pad2)") (class "Default")
      (node (ref "JP4") (pin "2") (pinfunction "2_2") (pintype "passive"))
    )
    (net (code "264") (name "unconnected-(JP4-Pad3)") (class "Default")
      (node (ref "JP4") (pin "3") (pinfunction "3_3") (pintype "passive"))
    )
    (net (code "265") (name "unconnected-(JP4-Pad4)") (class "Default")
      (node (ref "JP4") (pin "4") (pinfunction "4_4") (pintype "passive"))
    )
    (net (code "266") (name "unconnected-(JP4-Pad5)") (class "Default")
      (node (ref "JP4") (pin "5") (pinfunction "5_5") (pintype "passive"))
    )
    (net (code "267") (name "unconnected-(JP4-Pad6)") (class "Default")
      (node (ref "JP4") (pin "6") (pinfunction "6_6") (pintype "passive"))
    )
    (net (code "268") (name "unconnected-(JP4-Pad7)") (class "Default")
      (node (ref "JP4") (pin "7") (pinfunction "7_7") (pintype "passive"))
    )
    (net (code "269") (name "unconnected-(JP4-Pad8)") (class "Default")
      (node (ref "JP4") (pin "8") (pinfunction "8_8") (pintype "passive"))
    )
    (net (code "270") (name "unconnected-(JP4-Pad9)") (class "Default")
      (node (ref "JP4") (pin "9") (pinfunction "9_9") (pintype "passive"))
    )
    (net (code "271") (name "unconnected-(JP4-Pad10)") (class "Default")
      (node (ref "JP4") (pin "10") (pinfunction "10_10") (pintype "passive"))
    )
    (net (code "272") (name "unconnected-(JP4-Pad11)") (class "Default")
      (node (ref "JP4") (pin "11") (pinfunction "11_11") (pintype "passive"))
    )
    (net (code "273") (name "unconnected-(JP4-Pad12)") (class "Default")
      (node (ref "JP4") (pin "12") (pinfunction "12_12") (pintype "passive"))
    )
    (net (code "274") (name "unconnected-(JP4-Pad13)") (class "Default")
      (node (ref "JP4") (pin "13") (pinfunction "13_13") (pintype "passive"))
    )
    (net (code "275") (name "unconnected-(JP4-Pad14)") (class "Default")
      (node (ref "JP4") (pin "14") (pinfunction "14_14") (pintype "passive"))
    )
    (net (code "276") (name "unconnected-(JP4-Pad15)") (class "Default")
      (node (ref "JP4") (pin "15") (pinfunction "15_15") (pintype "passive"))
    )
    (net (code "277") (name "unconnected-(JP4-Pad16)") (class "Default")
      (node (ref "JP4") (pin "16") (pinfunction "16_16") (pintype "passive"))
    )
    (net (code "278") (name "unconnected-(U1-CLKIN1*-Pad26)") (class "Default")
      (node (ref "U1") (pin "26") (pinfunction "CLKIN1*_26") (pintype "passive+no_connect"))
    )
    (net (code "279") (name "unconnected-(U1-CLKIN1-Pad27)") (class "Default")
      (node (ref "U1") (pin "27") (pinfunction "CLKIN1_27") (pintype "passive+no_connect"))
    )
    (net (code "280") (name "unconnected-(U1-NC-Pad25)") (class "Default")
      (node (ref "U1") (pin "25") (pinfunction "NC_25") (pintype "passive+no_connect"))
    )
    (net (code "281") (name "unconnected-(U1-OSCIN-Pad11)") (class "Default")
      (node (ref "U1") (pin "11") (pinfunction "OSCIN_11") (pintype "passive+no_connect"))
    )
    (net (code "282") (name "unconnected-(U1-OSCOUT-Pad12)") (class "Default")
      (node (ref "U1") (pin "12") (pinfunction "OSCOUT_12") (pintype "passive+no_connect"))
    )
    (net (code "283") (name "unconnected-(U1-REFOUT-Pad29)") (class "Default")
      (node (ref "U1") (pin "29") (pinfunction "REFOUT_29") (pintype "passive+no_connect"))
    )
  )
)
